# keymap.net
KiCad netlist of a schematic drawn in Altium Designer
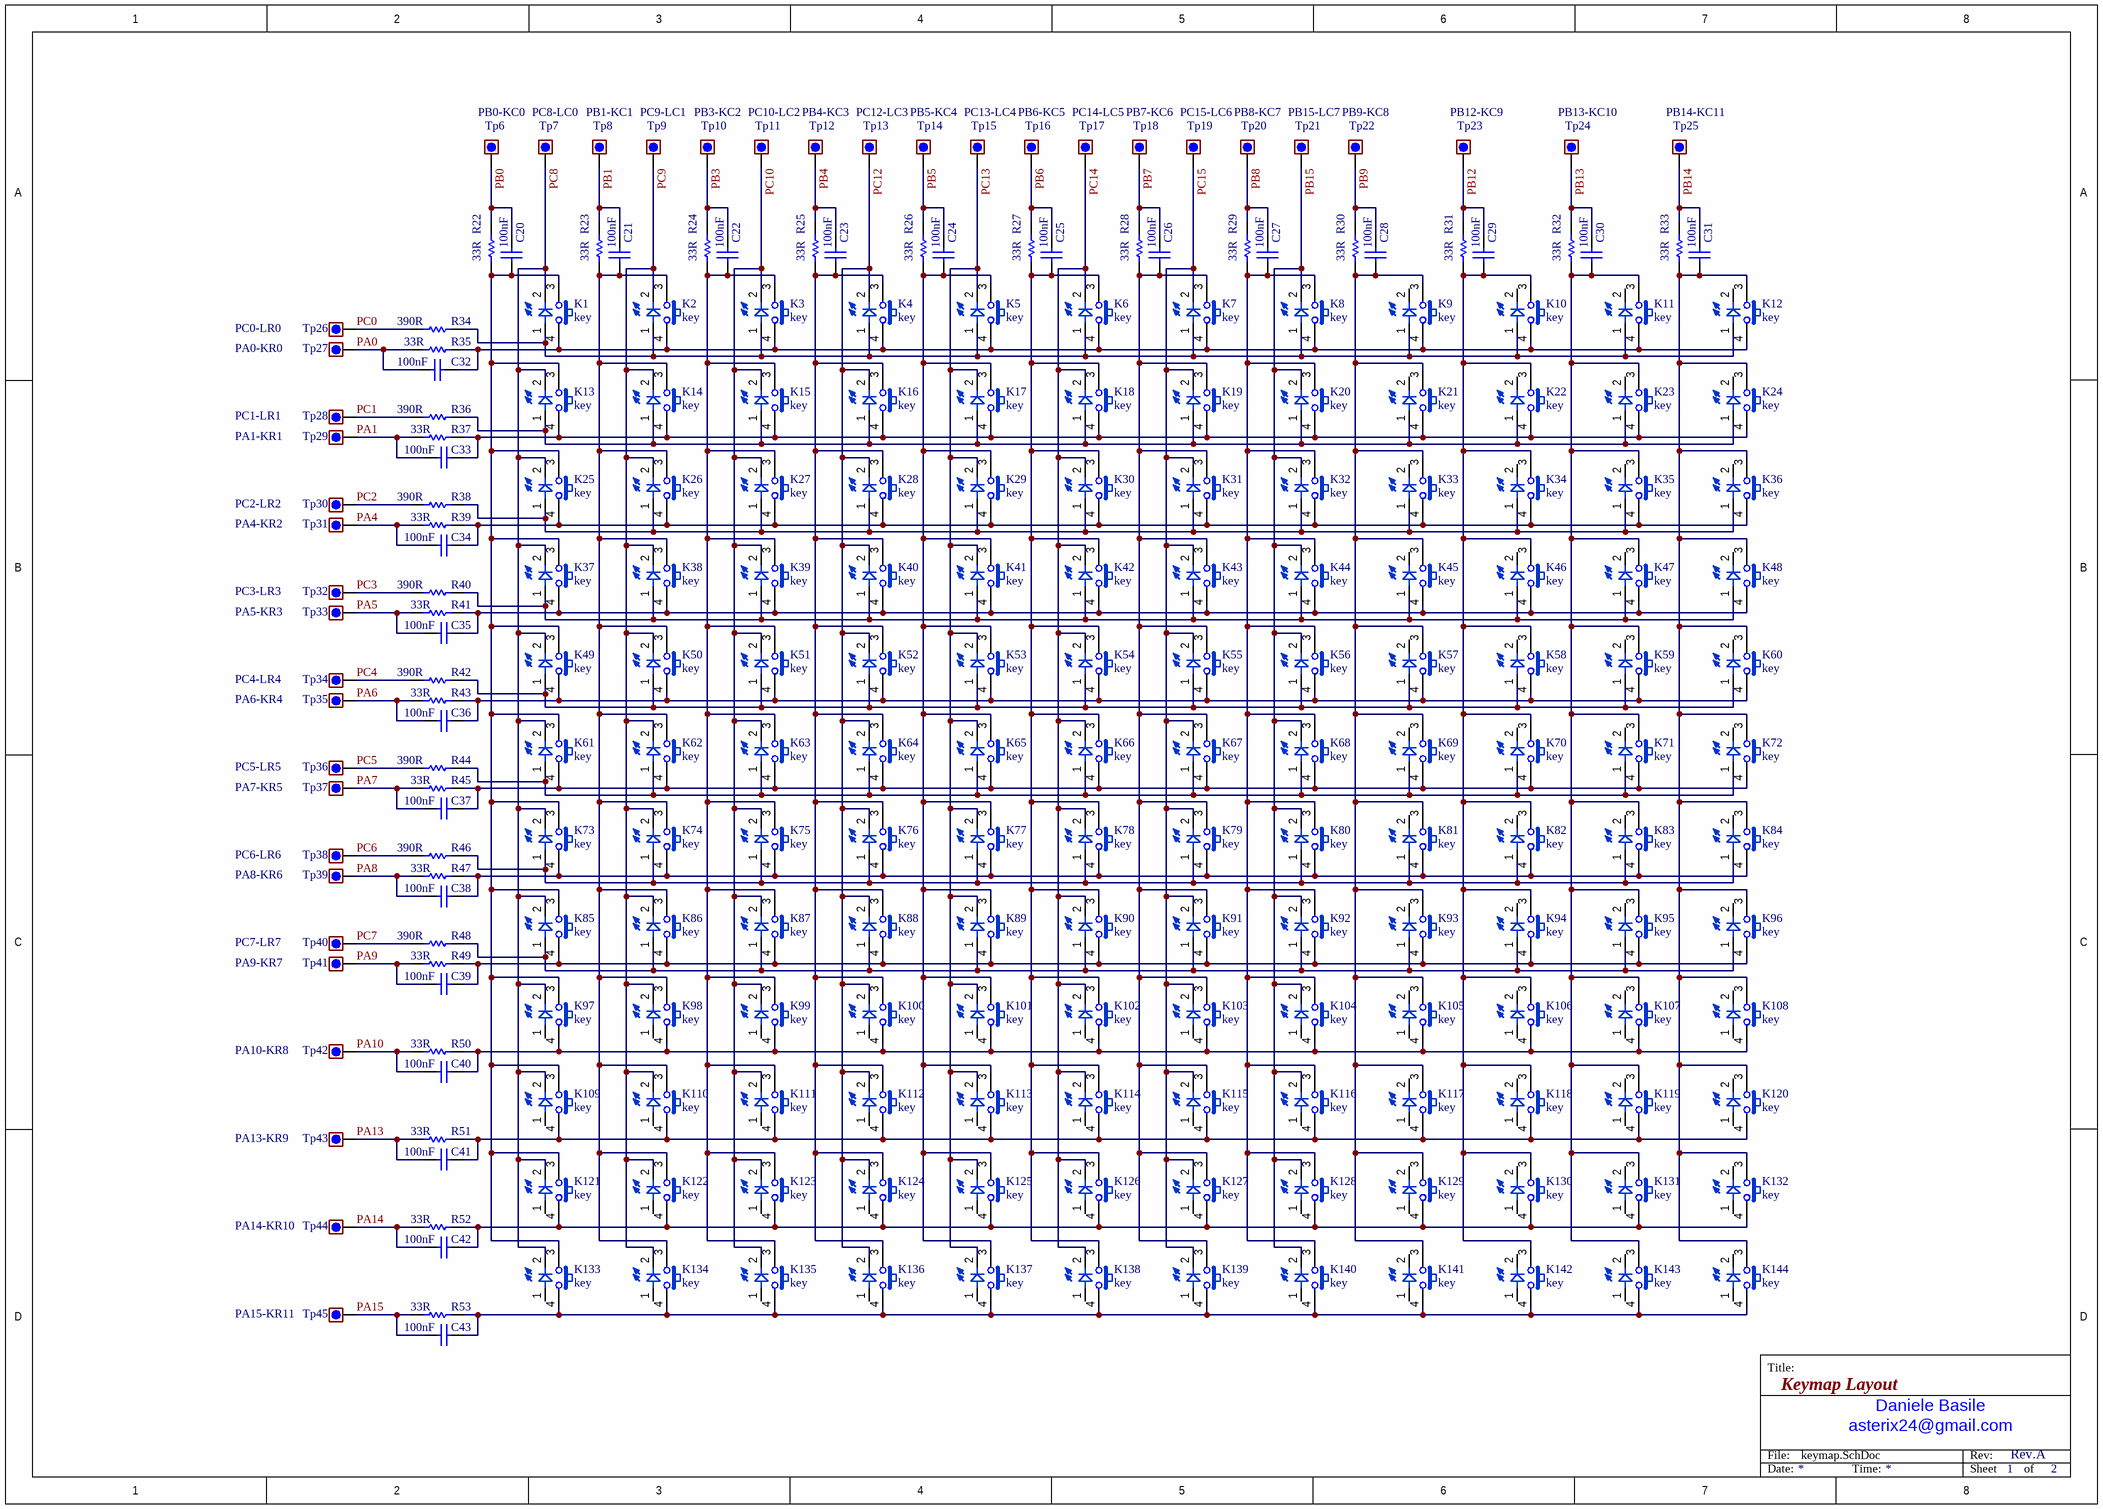
[diagram p0: keymap.SchDoc]

(export (version "E")
  (design (tool "Eeschema 10.0.6"))
  (components
    (comp (ref "C20")
      (value "100nF")
      (footprint "0603_[1608]")
      (description "Ceramic X7R 50V")
      (fields (field (name "PUBLISHER") "Altium Limited"))
      (libsource (lib "DEVELER_Library") (part "Cap"))
    )
    (comp (ref "C21")
      (value "100nF")
      (footprint "0603_[1608]")
      (description "Ceramic X7R 50V")
      (fields (field (name "PUBLISHER") "Altium Limited"))
      (libsource (lib "DEVELER_Library") (part "Cap"))
    )
    (comp (ref "C22")
      (value "100nF")
      (footprint "0603_[1608]")
      (description "Ceramic X7R 50V")
      (fields (field (name "PUBLISHER") "Altium Limited"))
      (libsource (lib "DEVELER_Library") (part "Cap"))
    )
    (comp (ref "C23")
      (value "100nF")
      (footprint "0603_[1608]")
      (description "Ceramic X7R 50V")
      (fields (field (name "PUBLISHER") "Altium Limited"))
      (libsource (lib "DEVELER_Library") (part "Cap"))
    )
    (comp (ref "C24")
      (value "100nF")
      (footprint "0603_[1608]")
      (description "Ceramic X7R 50V")
      (fields (field (name "PUBLISHER") "Altium Limited"))
      (libsource (lib "DEVELER_Library") (part "Cap"))
    )
    (comp (ref "C25")
      (value "100nF")
      (footprint "0603_[1608]")
      (description "Ceramic X7R 50V")
      (fields (field (name "PUBLISHER") "Altium Limited"))
      (libsource (lib "DEVELER_Library") (part "Cap"))
    )
    (comp (ref "C26")
      (value "100nF")
      (footprint "0603_[1608]")
      (description "Ceramic X7R 50V")
      (fields (field (name "PUBLISHER") "Altium Limited"))
      (libsource (lib "DEVELER_Library") (part "Cap"))
    )
    (comp (ref "C27")
      (value "100nF")
      (footprint "0603_[1608]")
      (description "Ceramic X7R 50V")
      (fields (field (name "PUBLISHER") "Altium Limited"))
      (libsource (lib "DEVELER_Library") (part "Cap"))
    )
    (comp (ref "C28")
      (value "100nF")
      (footprint "0603_[1608]")
      (description "Ceramic X7R 50V")
      (fields (field (name "PUBLISHER") "Altium Limited"))
      (libsource (lib "DEVELER_Library") (part "Cap"))
    )
    (comp (ref "C29")
      (value "100nF")
      (footprint "0603_[1608]")
      (description "Ceramic X7R 50V")
      (fields (field (name "PUBLISHER") "Altium Limited"))
      (libsource (lib "DEVELER_Library") (part "Cap"))
    )
    (comp (ref "C30")
      (value "100nF")
      (footprint "0603_[1608]")
      (description "Ceramic X7R 50V")
      (fields (field (name "PUBLISHER") "Altium Limited"))
      (libsource (lib "DEVELER_Library") (part "Cap"))
    )
    (comp (ref "C31")
      (value "100nF")
      (footprint "0603_[1608]")
      (description "Ceramic X7R 50V")
      (fields (field (name "PUBLISHER") "Altium Limited"))
      (libsource (lib "DEVELER_Library") (part "Cap"))
    )
    (comp (ref "C32")
      (value "100nF")
      (footprint "0603_[1608]")
      (description "Ceramic X7R 50V")
      (fields (field (name "PUBLISHER") "Altium Limited"))
      (libsource (lib "DEVELER_Library") (part "Cap"))
    )
    (comp (ref "C33")
      (value "100nF")
      (footprint "0603_[1608]")
      (description "Ceramic X7R 50V")
      (fields (field (name "PUBLISHER") "Altium Limited"))
      (libsource (lib "DEVELER_Library") (part "Cap"))
    )
    (comp (ref "C34")
      (value "100nF")
      (footprint "0603_[1608]")
      (description "Ceramic X7R 50V")
      (fields (field (name "PUBLISHER") "Altium Limited"))
      (libsource (lib "DEVELER_Library") (part "Cap"))
    )
    (comp (ref "C35")
      (value "100nF")
      (footprint "0603_[1608]")
      (description "Ceramic X7R 50V")
      (fields (field (name "PUBLISHER") "Altium Limited"))
      (libsource (lib "DEVELER_Library") (part "Cap"))
    )
    (comp (ref "C36")
      (value "100nF")
      (footprint "0603_[1608]")
      (description "Ceramic X7R 50V")
      (fields (field (name "PUBLISHER") "Altium Limited"))
      (libsource (lib "DEVELER_Library") (part "Cap"))
    )
    (comp (ref "C37")
      (value "100nF")
      (footprint "0603_[1608]")
      (description "Ceramic X7R 50V")
      (fields (field (name "PUBLISHER") "Altium Limited"))
      (libsource (lib "DEVELER_Library") (part "Cap"))
    )
    (comp (ref "C38")
      (value "100nF")
      (footprint "0603_[1608]")
      (description "Ceramic X7R 50V")
      (fields (field (name "PUBLISHER") "Altium Limited"))
      (libsource (lib "DEVELER_Library") (part "Cap"))
    )
    (comp (ref "C39")
      (value "100nF")
      (footprint "0603_[1608]")
      (description "Ceramic X7R 50V")
      (fields (field (name "PUBLISHER") "Altium Limited"))
      (libsource (lib "DEVELER_Library") (part "Cap"))
    )
    (comp (ref "C40")
      (value "100nF")
      (footprint "0603_[1608]")
      (description "Ceramic X7R 50V")
      (fields (field (name "PUBLISHER") "Altium Limited"))
      (libsource (lib "DEVELER_Library") (part "Cap"))
    )
    (comp (ref "C41")
      (value "100nF")
      (footprint "0603_[1608]")
      (description "Ceramic X7R 50V")
      (fields (field (name "PUBLISHER") "Altium Limited"))
      (libsource (lib "DEVELER_Library") (part "Cap"))
    )
    (comp (ref "C42")
      (value "100nF")
      (footprint "0603_[1608]")
      (description "Ceramic X7R 50V")
      (fields (field (name "PUBLISHER") "Altium Limited"))
      (libsource (lib "DEVELER_Library") (part "Cap"))
    )
    (comp (ref "C43")
      (value "100nF")
      (footprint "0603_[1608]")
      (description "Ceramic X7R 50V")
      (fields (field (name "PUBLISHER") "Altium Limited"))
      (libsource (lib "DEVELER_Library") (part "Cap"))
    )
    (comp (ref "K1")
      (value "key")
      (description "CherryMx key button.")
      (libsource (lib "develer_library") (part "keybutton_cherryMX"))
    )
    (comp (ref "K2")
      (value "key")
      (description "CherryMx key button.")
      (libsource (lib "develer_library") (part "keybutton_cherryMX"))
    )
    (comp (ref "K3")
      (value "key")
      (description "CherryMx key button.")
      (libsource (lib "develer_library") (part "keybutton_cherryMX"))
    )
    (comp (ref "K4")
      (value "key")
      (description "CherryMx key button.")
      (libsource (lib "develer_library") (part "keybutton_cherryMX"))
    )
    (comp (ref "K5")
      (value "key")
      (description "CherryMx key button.")
      (libsource (lib "develer_library") (part "keybutton_cherryMX"))
    )
    (comp (ref "K6")
      (value "key")
      (description "CherryMx key button.")
      (libsource (lib "develer_library") (part "keybutton_cherryMX"))
    )
    (comp (ref "K7")
      (value "key")
      (description "CherryMx key button.")
      (libsource (lib "develer_library") (part "keybutton_cherryMX"))
    )
    (comp (ref "K8")
      (value "key")
      (description "CherryMx key button.")
      (libsource (lib "develer_library") (part "keybutton_cherryMX"))
    )
    (comp (ref "K9")
      (value "key")
      (description "CherryMx key button.")
      (libsource (lib "develer_library") (part "keybutton_cherryMX"))
    )
    (comp (ref "K10")
      (value "key")
      (description "CherryMx key button.")
      (libsource (lib "develer_library") (part "keybutton_cherryMX"))
    )
    (comp (ref "K11")
      (value "key")
      (description "CherryMx key button.")
      (libsource (lib "develer_library") (part "keybutton_cherryMX"))
    )
    (comp (ref "K12")
      (value "key")
      (description "CherryMx key button.")
      (libsource (lib "develer_library") (part "keybutton_cherryMX"))
    )
    (comp (ref "K13")
      (value "key")
      (description "CherryMx key button.")
      (libsource (lib "develer_library") (part "keybutton_cherryMX"))
    )
    (comp (ref "K14")
      (value "key")
      (description "CherryMx key button.")
      (libsource (lib "develer_library") (part "keybutton_cherryMX"))
    )
    (comp (ref "K15")
      (value "key")
      (description "CherryMx key button.")
      (libsource (lib "develer_library") (part "keybutton_cherryMX"))
    )
    (comp (ref "K16")
      (value "key")
      (description "CherryMx key button.")
      (libsource (lib "develer_library") (part "keybutton_cherryMX"))
    )
    (comp (ref "K17")
      (value "key")
      (description "CherryMx key button.")
      (libsource (lib "develer_library") (part "keybutton_cherryMX"))
    )
    (comp (ref "K18")
      (value "key")
      (description "CherryMx key button.")
      (libsource (lib "develer_library") (part "keybutton_cherryMX"))
    )
    (comp (ref "K19")
      (value "key")
      (description "CherryMx key button.")
      (libsource (lib "develer_library") (part "keybutton_cherryMX"))
    )
    (comp (ref "K20")
      (value "key")
      (description "CherryMx key button.")
      (libsource (lib "develer_library") (part "keybutton_cherryMX"))
    )
    (comp (ref "K21")
      (value "key")
      (description "CherryMx key button.")
      (libsource (lib "develer_library") (part "keybutton_cherryMX"))
    )
    (comp (ref "K22")
      (value "key")
      (description "CherryMx key button.")
      (libsource (lib "develer_library") (part "keybutton_cherryMX"))
    )
    (comp (ref "K23")
      (value "key")
      (description "CherryMx key button.")
      (libsource (lib "develer_library") (part "keybutton_cherryMX"))
    )
    (comp (ref "K24")
      (value "key")
      (description "CherryMx key button.")
      (libsource (lib "develer_library") (part "keybutton_cherryMX"))
    )
    (comp (ref "K25")
      (value "key")
      (description "CherryMx key button.")
      (libsource (lib "develer_library") (part "keybutton_cherryMX"))
    )
    (comp (ref "K26")
      (value "key")
      (description "CherryMx key button.")
      (libsource (lib "develer_library") (part "keybutton_cherryMX"))
    )
    (comp (ref "K27")
      (value "key")
      (description "CherryMx key button.")
      (libsource (lib "develer_library") (part "keybutton_cherryMX"))
    )
    (comp (ref "K28")
      (value "key")
      (description "CherryMx key button.")
      (libsource (lib "develer_library") (part "keybutton_cherryMX"))
    )
    (comp (ref "K29")
      (value "key")
      (description "CherryMx key button.")
      (libsource (lib "develer_library") (part "keybutton_cherryMX"))
    )
    (comp (ref "K30")
      (value "key")
      (description "CherryMx key button.")
      (libsource (lib "develer_library") (part "keybutton_cherryMX"))
    )
    (comp (ref "K31")
      (value "key")
      (description "CherryMx key button.")
      (libsource (lib "develer_library") (part "keybutton_cherryMX"))
    )
    (comp (ref "K32")
      (value "key")
      (description "CherryMx key button.")
      (libsource (lib "develer_library") (part "keybutton_cherryMX"))
    )
    (comp (ref "K33")
      (value "key")
      (description "CherryMx key button.")
      (libsource (lib "develer_library") (part "keybutton_cherryMX"))
    )
    (comp (ref "K34")
      (value "key")
      (description "CherryMx key button.")
      (libsource (lib "develer_library") (part "keybutton_cherryMX"))
    )
    (comp (ref "K35")
      (value "key")
      (description "CherryMx key button.")
      (libsource (lib "develer_library") (part "keybutton_cherryMX"))
    )
    (comp (ref "K36")
      (value "key")
      (description "CherryMx key button.")
      (libsource (lib "develer_library") (part "keybutton_cherryMX"))
    )
    (comp (ref "K37")
      (value "key")
      (description "CherryMx key button.")
      (libsource (lib "develer_library") (part "keybutton_cherryMX"))
    )
    (comp (ref "K38")
      (value "key")
      (description "CherryMx key button.")
      (libsource (lib "develer_library") (part "keybutton_cherryMX"))
    )
    (comp (ref "K39")
      (value "key")
      (description "CherryMx key button.")
      (libsource (lib "develer_library") (part "keybutton_cherryMX"))
    )
    (comp (ref "K40")
      (value "key")
      (description "CherryMx key button.")
      (libsource (lib "develer_library") (part "keybutton_cherryMX"))
    )
    (comp (ref "K41")
      (value "key")
      (description "CherryMx key button.")
      (libsource (lib "develer_library") (part "keybutton_cherryMX"))
    )
    (comp (ref "K42")
      (value "key")
      (description "CherryMx key button.")
      (libsource (lib "develer_library") (part "keybutton_cherryMX"))
    )
    (comp (ref "K43")
      (value "key")
      (description "CherryMx key button.")
      (libsource (lib "develer_library") (part "keybutton_cherryMX"))
    )
    (comp (ref "K44")
      (value "key")
      (description "CherryMx key button.")
      (libsource (lib "develer_library") (part "keybutton_cherryMX"))
    )
    (comp (ref "K45")
      (value "key")
      (description "CherryMx key button.")
      (libsource (lib "develer_library") (part "keybutton_cherryMX"))
    )
    (comp (ref "K46")
      (value "key")
      (description "CherryMx key button.")
      (libsource (lib "develer_library") (part "keybutton_cherryMX"))
    )
    (comp (ref "K47")
      (value "key")
      (description "CherryMx key button.")
      (libsource (lib "develer_library") (part "keybutton_cherryMX"))
    )
    (comp (ref "K48")
      (value "key")
      (description "CherryMx key button.")
      (libsource (lib "develer_library") (part "keybutton_cherryMX"))
    )
    (comp (ref "K49")
      (value "key")
      (description "CherryMx key button.")
      (libsource (lib "develer_library") (part "keybutton_cherryMX"))
    )
    (comp (ref "K50")
      (value "key")
      (description "CherryMx key button.")
      (libsource (lib "develer_library") (part "keybutton_cherryMX"))
    )
    (comp (ref "K51")
      (value "key")
      (description "CherryMx key button.")
      (libsource (lib "develer_library") (part "keybutton_cherryMX"))
    )
    (comp (ref "K52")
      (value "key")
      (description "CherryMx key button.")
      (libsource (lib "develer_library") (part "keybutton_cherryMX"))
    )
    (comp (ref "K53")
      (value "key")
      (description "CherryMx key button.")
      (libsource (lib "develer_library") (part "keybutton_cherryMX"))
    )
    (comp (ref "K54")
      (value "key")
      (description "CherryMx key button.")
      (libsource (lib "develer_library") (part "keybutton_cherryMX"))
    )
    (comp (ref "K55")
      (value "key")
      (description "CherryMx key button.")
      (libsource (lib "develer_library") (part "keybutton_cherryMX"))
    )
    (comp (ref "K56")
      (value "key")
      (description "CherryMx key button.")
      (libsource (lib "develer_library") (part "keybutton_cherryMX"))
    )
    (comp (ref "K57")
      (value "key")
      (description "CherryMx key button.")
      (libsource (lib "develer_library") (part "keybutton_cherryMX"))
    )
    (comp (ref "K58")
      (value "key")
      (description "CherryMx key button.")
      (libsource (lib "develer_library") (part "keybutton_cherryMX"))
    )
    (comp (ref "K59")
      (value "key")
      (description "CherryMx key button.")
      (libsource (lib "develer_library") (part "keybutton_cherryMX"))
    )
    (comp (ref "K60")
      (value "key")
      (description "CherryMx key button.")
      (libsource (lib "develer_library") (part "keybutton_cherryMX"))
    )
    (comp (ref "K61")
      (value "key")
      (description "CherryMx key button.")
      (libsource (lib "develer_library") (part "keybutton_cherryMX"))
    )
    (comp (ref "K62")
      (value "key")
      (description "CherryMx key button.")
      (libsource (lib "develer_library") (part "keybutton_cherryMX"))
    )
    (comp (ref "K63")
      (value "key")
      (description "CherryMx key button.")
      (libsource (lib "develer_library") (part "keybutton_cherryMX"))
    )
    (comp (ref "K64")
      (value "key")
      (description "CherryMx key button.")
      (libsource (lib "develer_library") (part "keybutton_cherryMX"))
    )
    (comp (ref "K65")
      (value "key")
      (description "CherryMx key button.")
      (libsource (lib "develer_library") (part "keybutton_cherryMX"))
    )
    (comp (ref "K66")
      (value "key")
      (description "CherryMx key button.")
      (libsource (lib "develer_library") (part "keybutton_cherryMX"))
    )
    (comp (ref "K67")
      (value "key")
      (description "CherryMx key button.")
      (libsource (lib "develer_library") (part "keybutton_cherryMX"))
    )
    (comp (ref "K68")
      (value "key")
      (description "CherryMx key button.")
      (libsource (lib "develer_library") (part "keybutton_cherryMX"))
    )
    (comp (ref "K69")
      (value "key")
      (description "CherryMx key button.")
      (libsource (lib "develer_library") (part "keybutton_cherryMX"))
    )
    (comp (ref "K70")
      (value "key")
      (description "CherryMx key button.")
      (libsource (lib "develer_library") (part "keybutton_cherryMX"))
    )
    (comp (ref "K71")
      (value "key")
      (description "CherryMx key button.")
      (libsource (lib "develer_library") (part "keybutton_cherryMX"))
    )
    (comp (ref "K72")
      (value "key")
      (description "CherryMx key button.")
      (libsource (lib "develer_library") (part "keybutton_cherryMX"))
    )
    (comp (ref "K73")
      (value "key")
      (description "CherryMx key button.")
      (libsource (lib "develer_library") (part "keybutton_cherryMX"))
    )
    (comp (ref "K74")
      (value "key")
      (description "CherryMx key button.")
      (libsource (lib "develer_library") (part "keybutton_cherryMX"))
    )
    (comp (ref "K75")
      (value "key")
      (description "CherryMx key button.")
      (libsource (lib "develer_library") (part "keybutton_cherryMX"))
    )
    (comp (ref "K76")
      (value "key")
      (description "CherryMx key button.")
      (libsource (lib "develer_library") (part "keybutton_cherryMX"))
    )
    (comp (ref "K77")
      (value "key")
      (description "CherryMx key button.")
      (libsource (lib "develer_library") (part "keybutton_cherryMX"))
    )
    (comp (ref "K78")
      (value "key")
      (description "CherryMx key button.")
      (libsource (lib "develer_library") (part "keybutton_cherryMX"))
    )
    (comp (ref "K79")
      (value "key")
      (description "CherryMx key button.")
      (libsource (lib "develer_library") (part "keybutton_cherryMX"))
    )
    (comp (ref "K80")
      (value "key")
      (description "CherryMx key button.")
      (libsource (lib "develer_library") (part "keybutton_cherryMX"))
    )
    (comp (ref "K81")
      (value "key")
      (description "CherryMx key button.")
      (libsource (lib "develer_library") (part "keybutton_cherryMX"))
    )
    (comp (ref "K82")
      (value "key")
      (description "CherryMx key button.")
      (libsource (lib "develer_library") (part "keybutton_cherryMX"))
    )
    (comp (ref "K83")
      (value "key")
      (description "CherryMx key button.")
      (libsource (lib "develer_library") (part "keybutton_cherryMX"))
    )
    (comp (ref "K84")
      (value "key")
      (description "CherryMx key button.")
      (libsource (lib "develer_library") (part "keybutton_cherryMX"))
    )
    (comp (ref "K85")
      (value "key")
      (description "CherryMx key button.")
      (libsource (lib "develer_library") (part "keybutton_cherryMX"))
    )
    (comp (ref "K86")
      (value "key")
      (description "CherryMx key button.")
      (libsource (lib "develer_library") (part "keybutton_cherryMX"))
    )
    (comp (ref "K87")
      (value "key")
      (description "CherryMx key button.")
      (libsource (lib "develer_library") (part "keybutton_cherryMX"))
    )
    (comp (ref "K88")
      (value "key")
      (description "CherryMx key button.")
      (libsource (lib "develer_library") (part "keybutton_cherryMX"))
    )
    (comp (ref "K89")
      (value "key")
      (description "CherryMx key button.")
      (libsource (lib "develer_library") (part "keybutton_cherryMX"))
    )
    (comp (ref "K90")
      (value "key")
      (description "CherryMx key button.")
      (libsource (lib "develer_library") (part "keybutton_cherryMX"))
    )
    (comp (ref "K91")
      (value "key")
      (description "CherryMx key button.")
      (libsource (lib "develer_library") (part "keybutton_cherryMX"))
    )
    (comp (ref "K92")
      (value "key")
      (description "CherryMx key button.")
      (libsource (lib "develer_library") (part "keybutton_cherryMX"))
    )
    (comp (ref "K93")
      (value "key")
      (description "CherryMx key button.")
      (libsource (lib "develer_library") (part "keybutton_cherryMX"))
    )
    (comp (ref "K94")
      (value "key")
      (description "CherryMx key button.")
      (libsource (lib "develer_library") (part "keybutton_cherryMX"))
    )
    (comp (ref "K95")
      (value "key")
      (description "CherryMx key button.")
      (libsource (lib "develer_library") (part "keybutton_cherryMX"))
    )
    (comp (ref "K96")
      (value "key")
      (description "CherryMx key button.")
      (libsource (lib "develer_library") (part "keybutton_cherryMX"))
    )
    (comp (ref "K97")
      (value "key")
      (description "CherryMx key button.")
      (libsource (lib "develer_library") (part "keybutton_cherryMX"))
    )
    (comp (ref "K98")
      (value "key")
      (description "CherryMx key button.")
      (libsource (lib "develer_library") (part "keybutton_cherryMX"))
    )
    (comp (ref "K99")
      (value "key")
      (description "CherryMx key button.")
      (libsource (lib "develer_library") (part "keybutton_cherryMX"))
    )
    (comp (ref "K100")
      (value "key")
      (description "CherryMx key button.")
      (libsource (lib "develer_library") (part "keybutton_cherryMX"))
    )
    (comp (ref "K101")
      (value "key")
      (description "CherryMx key button.")
      (libsource (lib "develer_library") (part "keybutton_cherryMX"))
    )
    (comp (ref "K102")
      (value "key")
      (description "CherryMx key button.")
      (libsource (lib "develer_library") (part "keybutton_cherryMX"))
    )
    (comp (ref "K103")
      (value "key")
      (description "CherryMx key button.")
      (libsource (lib "develer_library") (part "keybutton_cherryMX"))
    )
    (comp (ref "K104")
      (value "key")
      (description "CherryMx key button.")
      (libsource (lib "develer_library") (part "keybutton_cherryMX"))
    )
    (comp (ref "K105")
      (value "key")
      (description "CherryMx key button.")
      (libsource (lib "develer_library") (part "keybutton_cherryMX"))
    )
    (comp (ref "K106")
      (value "key")
      (description "CherryMx key button.")
      (libsource (lib "develer_library") (part "keybutton_cherryMX"))
    )
    (comp (ref "K107")
      (value "key")
      (description "CherryMx key button.")
      (libsource (lib "develer_library") (part "keybutton_cherryMX"))
    )
    (comp (ref "K108")
      (value "key")
      (description "CherryMx key button.")
      (libsource (lib "develer_library") (part "keybutton_cherryMX"))
    )
    (comp (ref "K109")
      (value "key")
      (description "CherryMx key button.")
      (libsource (lib "develer_library") (part "keybutton_cherryMX"))
    )
    (comp (ref "K110")
      (value "key")
      (description "CherryMx key button.")
      (libsource (lib "develer_library") (part "keybutton_cherryMX"))
    )
    (comp (ref "K111")
      (value "key")
      (description "CherryMx key button.")
      (libsource (lib "develer_library") (part "keybutton_cherryMX"))
    )
    (comp (ref "K112")
      (value "key")
      (description "CherryMx key button.")
      (libsource (lib "develer_library") (part "keybutton_cherryMX"))
    )
    (comp (ref "K113")
      (value "key")
      (description "CherryMx key button.")
      (libsource (lib "develer_library") (part "keybutton_cherryMX"))
    )
    (comp (ref "K114")
      (value "key")
      (description "CherryMx key button.")
      (libsource (lib "develer_library") (part "keybutton_cherryMX"))
    )
    (comp (ref "K115")
      (value "key")
      (description "CherryMx key button.")
      (libsource (lib "develer_library") (part "keybutton_cherryMX"))
    )
    (comp (ref "K116")
      (value "key")
      (description "CherryMx key button.")
      (libsource (lib "develer_library") (part "keybutton_cherryMX"))
    )
    (comp (ref "K117")
      (value "key")
      (description "CherryMx key button.")
      (libsource (lib "develer_library") (part "keybutton_cherryMX"))
    )
    (comp (ref "K118")
      (value "key")
      (description "CherryMx key button.")
      (libsource (lib "develer_library") (part "keybutton_cherryMX"))
    )
    (comp (ref "K119")
      (value "key")
      (description "CherryMx key button.")
      (libsource (lib "develer_library") (part "keybutton_cherryMX"))
    )
    (comp (ref "K120")
      (value "key")
      (description "CherryMx key button.")
      (libsource (lib "develer_library") (part "keybutton_cherryMX"))
    )
    (comp (ref "K121")
      (value "key")
      (description "CherryMx key button.")
      (libsource (lib "develer_library") (part "keybutton_cherryMX"))
    )
    (comp (ref "K122")
      (value "key")
      (description "CherryMx key button.")
      (libsource (lib "develer_library") (part "keybutton_cherryMX"))
    )
    (comp (ref "K123")
      (value "key")
      (description "CherryMx key button.")
      (libsource (lib "develer_library") (part "keybutton_cherryMX"))
    )
    (comp (ref "K124")
      (value "key")
      (description "CherryMx key button.")
      (libsource (lib "develer_library") (part "keybutton_cherryMX"))
    )
    (comp (ref "K125")
      (value "key")
      (description "CherryMx key button.")
      (libsource (lib "develer_library") (part "keybutton_cherryMX"))
    )
    (comp (ref "K126")
      (value "key")
      (description "CherryMx key button.")
      (libsource (lib "develer_library") (part "keybutton_cherryMX"))
    )
    (comp (ref "K127")
      (value "key")
      (description "CherryMx key button.")
      (libsource (lib "develer_library") (part "keybutton_cherryMX"))
    )
    (comp (ref "K128")
      (value "key")
      (description "CherryMx key button.")
      (libsource (lib "develer_library") (part "keybutton_cherryMX"))
    )
    (comp (ref "K129")
      (value "key")
      (description "CherryMx key button.")
      (libsource (lib "develer_library") (part "keybutton_cherryMX"))
    )
    (comp (ref "K130")
      (value "key")
      (description "CherryMx key button.")
      (libsource (lib "develer_library") (part "keybutton_cherryMX"))
    )
    (comp (ref "K131")
      (value "key")
      (description "CherryMx key button.")
      (libsource (lib "develer_library") (part "keybutton_cherryMX"))
    )
    (comp (ref "K132")
      (value "key")
      (description "CherryMx key button.")
      (libsource (lib "develer_library") (part "keybutton_cherryMX"))
    )
    (comp (ref "K133")
      (value "key")
      (description "CherryMx key button.")
      (libsource (lib "develer_library") (part "keybutton_cherryMX"))
    )
    (comp (ref "K134")
      (value "key")
      (description "CherryMx key button.")
      (libsource (lib "develer_library") (part "keybutton_cherryMX"))
    )
    (comp (ref "K135")
      (value "key")
      (description "CherryMx key button.")
      (libsource (lib "develer_library") (part "keybutton_cherryMX"))
    )
    (comp (ref "K136")
      (value "key")
      (description "CherryMx key button.")
      (libsource (lib "develer_library") (part "keybutton_cherryMX"))
    )
    (comp (ref "K137")
      (value "key")
      (description "CherryMx key button.")
      (libsource (lib "develer_library") (part "keybutton_cherryMX"))
    )
    (comp (ref "K138")
      (value "key")
      (description "CherryMx key button.")
      (libsource (lib "develer_library") (part "keybutton_cherryMX"))
    )
    (comp (ref "K139")
      (value "key")
      (description "CherryMx key button.")
      (libsource (lib "develer_library") (part "keybutton_cherryMX"))
    )
    (comp (ref "K140")
      (value "key")
      (description "CherryMx key button.")
      (libsource (lib "develer_library") (part "keybutton_cherryMX"))
    )
    (comp (ref "K141")
      (value "key")
      (description "CherryMx key button.")
      (libsource (lib "develer_library") (part "keybutton_cherryMX"))
    )
    (comp (ref "K142")
      (value "key")
      (description "CherryMx key button.")
      (libsource (lib "develer_library") (part "keybutton_cherryMX"))
    )
    (comp (ref "K143")
      (value "key")
      (description "CherryMx key button.")
      (libsource (lib "develer_library") (part "keybutton_cherryMX"))
    )
    (comp (ref "K144")
      (value "key")
      (description "CherryMx key button.")
      (libsource (lib "develer_library") (part "keybutton_cherryMX"))
    )
    (comp (ref "R22")
      (value "33R")
      (footprint "0402_[1005]")
      (description "Resistor")
      (fields (field (name "PUBLISHER") "Altium Limited"))
      (libsource (lib "simboli") (part "Res1"))
    )
    (comp (ref "R23")
      (value "33R")
      (footprint "0402_[1005]")
      (description "Resistor")
      (fields (field (name "PUBLISHER") "Altium Limited"))
      (libsource (lib "simboli") (part "Res1"))
    )
    (comp (ref "R24")
      (value "33R")
      (footprint "0402_[1005]")
      (description "Resistor")
      (fields (field (name "PUBLISHER") "Altium Limited"))
      (libsource (lib "simboli") (part "Res1"))
    )
    (comp (ref "R25")
      (value "33R")
      (footprint "0402_[1005]")
      (description "Resistor")
      (fields (field (name "PUBLISHER") "Altium Limited"))
      (libsource (lib "simboli") (part "Res1"))
    )
    (comp (ref "R26")
      (value "33R")
      (footprint "0402_[1005]")
      (description "Resistor")
      (fields (field (name "PUBLISHER") "Altium Limited"))
      (libsource (lib "simboli") (part "Res1"))
    )
    (comp (ref "R27")
      (value "33R")
      (footprint "0402_[1005]")
      (description "Resistor")
      (fields (field (name "PUBLISHER") "Altium Limited"))
      (libsource (lib "simboli") (part "Res1"))
    )
    (comp (ref "R28")
      (value "33R")
      (footprint "0402_[1005]")
      (description "Resistor")
      (fields (field (name "PUBLISHER") "Altium Limited"))
      (libsource (lib "simboli") (part "Res1"))
    )
    (comp (ref "R29")
      (value "33R")
      (footprint "0402_[1005]")
      (description "Resistor")
      (fields (field (name "PUBLISHER") "Altium Limited"))
      (libsource (lib "simboli") (part "Res1"))
    )
    (comp (ref "R30")
      (value "33R")
      (footprint "0402_[1005]")
      (description "Resistor")
      (fields (field (name "PUBLISHER") "Altium Limited"))
      (libsource (lib "simboli") (part "Res1"))
    )
    (comp (ref "R31")
      (value "33R")
      (footprint "0402_[1005]")
      (description "Resistor")
      (fields (field (name "PUBLISHER") "Altium Limited"))
      (libsource (lib "simboli") (part "Res1"))
    )
    (comp (ref "R32")
      (value "33R")
      (footprint "0402_[1005]")
      (description "Resistor")
      (fields (field (name "PUBLISHER") "Altium Limited"))
      (libsource (lib "simboli") (part "Res1"))
    )
    (comp (ref "R33")
      (value "33R")
      (footprint "0402_[1005]")
      (description "Resistor")
      (fields (field (name "PUBLISHER") "Altium Limited"))
      (libsource (lib "simboli") (part "Res1"))
    )
    (comp (ref "R34")
      (value "390R")
      (footprint "0402_[1005]")
      (description "Resistor")
      (fields (field (name "PUBLISHER") "Altium Limited"))
      (libsource (lib "simboli") (part "Res1"))
    )
    (comp (ref "R35")
      (value "33R")
      (footprint "0402_[1005]")
      (description "Resistor")
      (fields (field (name "PUBLISHER") "Altium Limited"))
      (libsource (lib "simboli") (part "Res1"))
    )
    (comp (ref "R36")
      (value "390R")
      (footprint "0402_[1005]")
      (description "Resistor")
      (fields (field (name "PUBLISHER") "Altium Limited"))
      (libsource (lib "simboli") (part "Res1"))
    )
    (comp (ref "R37")
      (value "33R")
      (footprint "0402_[1005]")
      (description "Resistor")
      (fields (field (name "PUBLISHER") "Altium Limited"))
      (libsource (lib "simboli") (part "Res1"))
    )
    (comp (ref "R38")
      (value "390R")
      (footprint "0402_[1005]")
      (description "Resistor")
      (fields (field (name "PUBLISHER") "Altium Limited"))
      (libsource (lib "simboli") (part "Res1"))
    )
    (comp (ref "R39")
      (value "33R")
      (footprint "0402_[1005]")
      (description "Resistor")
      (fields (field (name "PUBLISHER") "Altium Limited"))
      (libsource (lib "simboli") (part "Res1"))
    )
    (comp (ref "R40")
      (value "390R")
      (footprint "0402_[1005]")
      (description "Resistor")
      (fields (field (name "PUBLISHER") "Altium Limited"))
      (libsource (lib "simboli") (part "Res1"))
    )
    (comp (ref "R41")
      (value "33R")
      (footprint "0402_[1005]")
      (description "Resistor")
      (fields (field (name "PUBLISHER") "Altium Limited"))
      (libsource (lib "simboli") (part "Res1"))
    )
    (comp (ref "R42")
      (value "390R")
      (footprint "0402_[1005]")
      (description "Resistor")
      (fields (field (name "PUBLISHER") "Altium Limited"))
      (libsource (lib "simboli") (part "Res1"))
    )
    (comp (ref "R43")
      (value "33R")
      (footprint "0402_[1005]")
      (description "Resistor")
      (fields (field (name "PUBLISHER") "Altium Limited"))
      (libsource (lib "simboli") (part "Res1"))
    )
    (comp (ref "R44")
      (value "390R")
      (footprint "0402_[1005]")
      (description "Resistor")
      (fields (field (name "PUBLISHER") "Altium Limited"))
      (libsource (lib "simboli") (part "Res1"))
    )
    (comp (ref "R45")
      (value "33R")
      (footprint "0402_[1005]")
      (description "Resistor")
      (fields (field (name "PUBLISHER") "Altium Limited"))
      (libsource (lib "simboli") (part "Res1"))
    )
    (comp (ref "R46")
      (value "390R")
      (footprint "0402_[1005]")
      (description "Resistor")
      (fields (field (name "PUBLISHER") "Altium Limited"))
      (libsource (lib "simboli") (part "Res1"))
    )
    (comp (ref "R47")
      (value "33R")
      (footprint "0402_[1005]")
      (description "Resistor")
      (fields (field (name "PUBLISHER") "Altium Limited"))
      (libsource (lib "simboli") (part "Res1"))
    )
    (comp (ref "R48")
      (value "390R")
      (footprint "0402_[1005]")
      (description "Resistor")
      (fields (field (name "PUBLISHER") "Altium Limited"))
      (libsource (lib "simboli") (part "Res1"))
    )
    (comp (ref "R49")
      (value "33R")
      (footprint "0402_[1005]")
      (description "Resistor")
      (fields (field (name "PUBLISHER") "Altium Limited"))
      (libsource (lib "simboli") (part "Res1"))
    )
    (comp (ref "R50")
      (value "33R")
      (footprint "0402_[1005]")
      (description "Resistor")
      (fields (field (name "PUBLISHER") "Altium Limited"))
      (libsource (lib "simboli") (part "Res1"))
    )
    (comp (ref "R51")
      (value "33R")
      (footprint "0402_[1005]")
      (description "Resistor")
      (fields (field (name "PUBLISHER") "Altium Limited"))
      (libsource (lib "simboli") (part "Res1"))
    )
    (comp (ref "R52")
      (value "33R")
      (footprint "0402_[1005]")
      (description "Resistor")
      (fields (field (name "PUBLISHER") "Altium Limited"))
      (libsource (lib "simboli") (part "Res1"))
    )
    (comp (ref "R53")
      (value "33R")
      (footprint "0402_[1005]")
      (description "Resistor")
      (fields (field (name "PUBLISHER") "Altium Limited"))
      (libsource (lib "simboli") (part "Res1"))
    )
    (comp (ref "Tp6")
      (value "PB0-KC0")
      (footprint "TEST_POINT_THD_D1.8MM")
      (description "Test point")
      (libsource (lib "") (part "Test_point_1"))
    )
    (comp (ref "Tp7")
      (value "PC8-LC0")
      (footprint "TEST_POINT_THD_D1.8MM")
      (description "Test point")
      (libsource (lib "") (part "Test_point_1"))
    )
    (comp (ref "Tp8")
      (value "PB1-KC1")
      (footprint "TEST_POINT_THD_D1.8MM")
      (description "Test point")
      (libsource (lib "") (part "Test_point_1"))
    )
    (comp (ref "Tp9")
      (value "PC9-LC1")
      (footprint "TEST_POINT_THD_D1.8MM")
      (description "Test point")
      (libsource (lib "") (part "Test_point_1"))
    )
    (comp (ref "Tp10")
      (value "PB3-KC2")
      (footprint "TEST_POINT_THD_D1.8MM")
      (description "Test point")
      (libsource (lib "") (part "Test_point_1"))
    )
    (comp (ref "Tp11")
      (value "PC10-LC2")
      (footprint "TEST_POINT_THD_D1.8MM")
      (description "Test point")
      (libsource (lib "") (part "Test_point_1"))
    )
    (comp (ref "Tp12")
      (value "PB4-KC3")
      (footprint "TEST_POINT_THD_D1.8MM")
      (description "Test point")
      (libsource (lib "") (part "Test_point_1"))
    )
    (comp (ref "Tp13")
      (value "PC12-LC3")
      (footprint "TEST_POINT_THD_D1.8MM")
      (description "Test point")
      (libsource (lib "") (part "Test_point_1"))
    )
    (comp (ref "Tp14")
      (value "PB5-KC4")
      (footprint "TEST_POINT_THD_D1.8MM")
      (description "Test point")
      (libsource (lib "") (part "Test_point_1"))
    )
    (comp (ref "Tp15")
      (value "PC13-LC4")
      (footprint "TEST_POINT_THD_D1.8MM")
      (description "Test point")
      (libsource (lib "") (part "Test_point_1"))
    )
    (comp (ref "Tp16")
      (value "PB6-KC5")
      (footprint "TEST_POINT_THD_D1.8MM")
      (description "Test point")
      (libsource (lib "") (part "Test_point_1"))
    )
    (comp (ref "Tp17")
      (value "PC14-LC5")
      (footprint "TEST_POINT_THD_D1.8MM")
      (description "Test point")
      (libsource (lib "") (part "Test_point_1"))
    )
    (comp (ref "Tp18")
      (value "PB7-KC6")
      (footprint "TEST_POINT_THD_D1.8MM")
      (description "Test point")
      (libsource (lib "") (part "Test_point_1"))
    )
    (comp (ref "Tp19")
      (value "PC15-LC6")
      (footprint "TEST_POINT_THD_D1.8MM")
      (description "Test point")
      (libsource (lib "") (part "Test_point_1"))
    )
    (comp (ref "Tp20")
      (value "PB8-KC7")
      (footprint "TEST_POINT_THD_D1.8MM")
      (description "Test point")
      (libsource (lib "") (part "Test_point_1"))
    )
    (comp (ref "Tp21")
      (value "PB15-LC7")
      (footprint "TEST_POINT_THD_D1.8MM")
      (description "Test point")
      (libsource (lib "") (part "Test_point_1"))
    )
    (comp (ref "Tp22")
      (value "PB9-KC8")
      (footprint "TEST_POINT_THD_D1.8MM")
      (description "Test point")
      (libsource (lib "") (part "Test_point_1"))
    )
    (comp (ref "Tp23")
      (value "PB12-KC9")
      (footprint "TEST_POINT_THD_D1.8MM")
      (description "Test point")
      (libsource (lib "") (part "Test_point_1"))
    )
    (comp (ref "Tp24")
      (value "PB13-KC10")
      (footprint "TEST_POINT_THD_D1.8MM")
      (description "Test point")
      (libsource (lib "") (part "Test_point_1"))
    )
    (comp (ref "Tp25")
      (value "PB14-KC11")
      (footprint "TEST_POINT_THD_D1.8MM")
      (description "Test point")
      (libsource (lib "") (part "Test_point_1"))
    )
    (comp (ref "Tp26")
      (value "PC0-LR0")
      (footprint "TEST_POINT_THD_D1.8MM")
      (description "Test point")
      (libsource (lib "DEVELER_Library") (part "Test_point"))
    )
    (comp (ref "Tp27")
      (value "PA0-KR0")
      (footprint "TEST_POINT_THD_D1.8MM")
      (description "Test point")
      (libsource (lib "DEVELER_Library") (part "Test_point"))
    )
    (comp (ref "Tp28")
      (value "PC1-LR1")
      (footprint "TEST_POINT_THD_D1.8MM")
      (description "Test point")
      (libsource (lib "DEVELER_Library") (part "Test_point"))
    )
    (comp (ref "Tp29")
      (value "PA1-KR1")
      (footprint "TEST_POINT_THD_D1.8MM")
      (description "Test point")
      (libsource (lib "DEVELER_Library") (part "Test_point"))
    )
    (comp (ref "Tp30")
      (value "PC2-LR2")
      (footprint "TEST_POINT_THD_D1.8MM")
      (description "Test point")
      (libsource (lib "DEVELER_Library") (part "Test_point"))
    )
    (comp (ref "Tp31")
      (value "PA4-KR2")
      (footprint "TEST_POINT_THD_D1.8MM")
      (description "Test point")
      (libsource (lib "DEVELER_Library") (part "Test_point"))
    )
    (comp (ref "Tp32")
      (value "PC3-LR3")
      (footprint "TEST_POINT_THD_D1.8MM")
      (description "Test point")
      (libsource (lib "DEVELER_Library") (part "Test_point"))
    )
    (comp (ref "Tp33")
      (value "PA5-KR3")
      (footprint "TEST_POINT_THD_D1.8MM")
      (description "Test point")
      (libsource (lib "DEVELER_Library") (part "Test_point"))
    )
    (comp (ref "Tp34")
      (value "PC4-LR4")
      (footprint "TEST_POINT_THD_D1.8MM")
      (description "Test point")
      (libsource (lib "DEVELER_Library") (part "Test_point"))
    )
    (comp (ref "Tp35")
      (value "PA6-KR4")
      (footprint "TEST_POINT_THD_D1.8MM")
      (description "Test point")
      (libsource (lib "DEVELER_Library") (part "Test_point"))
    )
    (comp (ref "Tp36")
      (value "PC5-LR5")
      (footprint "TEST_POINT_THD_D1.8MM")
      (description "Test point")
      (libsource (lib "DEVELER_Library") (part "Test_point"))
    )
    (comp (ref "Tp37")
      (value "PA7-KR5")
      (footprint "TEST_POINT_THD_D1.8MM")
      (description "Test point")
      (libsource (lib "DEVELER_Library") (part "Test_point"))
    )
    (comp (ref "Tp38")
      (value "PC6-LR6")
      (footprint "TEST_POINT_THD_D1.8MM")
      (description "Test point")
      (libsource (lib "DEVELER_Library") (part "Test_point"))
    )
    (comp (ref "Tp39")
      (value "PA8-KR6")
      (footprint "TEST_POINT_THD_D1.8MM")
      (description "Test point")
      (libsource (lib "DEVELER_Library") (part "Test_point"))
    )
    (comp (ref "Tp40")
      (value "PC7-LR7")
      (footprint "TEST_POINT_THD_D1.8MM")
      (description "Test point")
      (libsource (lib "DEVELER_Library") (part "Test_point"))
    )
    (comp (ref "Tp41")
      (value "PA9-KR7")
      (footprint "TEST_POINT_THD_D1.8MM")
      (description "Test point")
      (libsource (lib "DEVELER_Library") (part "Test_point"))
    )
    (comp (ref "Tp42")
      (value "PA10-KR8")
      (footprint "TEST_POINT_THD_D1.8MM")
      (description "Test point")
      (libsource (lib "DEVELER_Library") (part "Test_point"))
    )
    (comp (ref "Tp43")
      (value "PA13-KR9")
      (footprint "TEST_POINT_THD_D1.8MM")
      (description "Test point")
      (libsource (lib "DEVELER_Library") (part "Test_point"))
    )
    (comp (ref "Tp44")
      (value "PA14-KR10")
      (footprint "TEST_POINT_THD_D1.8MM")
      (description "Test point")
      (libsource (lib "DEVELER_Library") (part "Test_point"))
    )
    (comp (ref "Tp45")
      (value "PA15-KR11")
      (footprint "TEST_POINT_THD_D1.8MM")
      (description "Test point")
      (libsource (lib "DEVELER_Library") (part "Test_point"))
    )
  )
  (nets
    (net (code "1") (name "/PA0") (class "Default")
      (node (ref "C32") (pin "1") (pinfunction "1_1") (pintype "passive"))
      (node (ref "R35") (pin "1") (pinfunction "1_1") (pintype "passive"))
      (node (ref "Tp27") (pin "1") (pinfunction "1_1") (pintype "passive"))
    )
    (net (code "2") (name "/PA1") (class "Default")
      (node (ref "C33") (pin "1") (pinfunction "1_1") (pintype "passive"))
      (node (ref "R37") (pin "1") (pinfunction "1_1") (pintype "passive"))
      (node (ref "Tp29") (pin "1") (pinfunction "1_1") (pintype "passive"))
    )
    (net (code "3") (name "/PA4") (class "Default")
      (node (ref "C34") (pin "1") (pinfunction "1_1") (pintype "passive"))
      (node (ref "R39") (pin "1") (pinfunction "1_1") (pintype "passive"))
      (node (ref "Tp31") (pin "1") (pinfunction "1_1") (pintype "passive"))
    )
    (net (code "4") (name "/PA5") (class "Default")
      (node (ref "C35") (pin "1") (pinfunction "1_1") (pintype "passive"))
      (node (ref "R41") (pin "1") (pinfunction "1_1") (pintype "passive"))
      (node (ref "Tp33") (pin "1") (pinfunction "1_1") (pintype "passive"))
    )
    (net (code "5") (name "/PA6") (class "Default")
      (node (ref "C36") (pin "1") (pinfunction "1_1") (pintype "passive"))
      (node (ref "R43") (pin "1") (pinfunction "1_1") (pintype "passive"))
      (node (ref "Tp35") (pin "1") (pinfunction "1_1") (pintype "passive"))
    )
    (net (code "6") (name "/PA7") (class "Default")
      (node (ref "C37") (pin "1") (pinfunction "1_1") (pintype "passive"))
      (node (ref "R45") (pin "1") (pinfunction "1_1") (pintype "passive"))
      (node (ref "Tp37") (pin "1") (pinfunction "1_1") (pintype "passive"))
    )
    (net (code "7") (name "/PA8") (class "Default")
      (node (ref "C38") (pin "1") (pinfunction "1_1") (pintype "passive"))
      (node (ref "R47") (pin "1") (pinfunction "1_1") (pintype "passive"))
      (node (ref "Tp39") (pin "1") (pinfunction "1_1") (pintype "passive"))
    )
    (net (code "8") (name "/PA9") (class "Default")
      (node (ref "C39") (pin "1") (pinfunction "1_1") (pintype "passive"))
      (node (ref "R49") (pin "1") (pinfunction "1_1") (pintype "passive"))
      (node (ref "Tp41") (pin "1") (pinfunction "1_1") (pintype "passive"))
    )
    (net (code "9") (name "/PA10") (class "Default")
      (node (ref "C40") (pin "1") (pinfunction "1_1") (pintype "passive"))
      (node (ref "R50") (pin "1") (pinfunction "1_1") (pintype "passive"))
      (node (ref "Tp42") (pin "1") (pinfunction "1_1") (pintype "passive"))
    )
    (net (code "10") (name "/PA13") (class "Default")
      (node (ref "C41") (pin "1") (pinfunction "1_1") (pintype "passive"))
      (node (ref "R51") (pin "1") (pinfunction "1_1") (pintype "passive"))
      (node (ref "Tp43") (pin "1") (pinfunction "1_1") (pintype "passive"))
    )
    (net (code "11") (name "/PA14") (class "Default")
      (node (ref "C42") (pin "1") (pinfunction "1_1") (pintype "passive"))
      (node (ref "R52") (pin "1") (pinfunction "1_1") (pintype "passive"))
      (node (ref "Tp44") (pin "1") (pinfunction "1_1") (pintype "passive"))
    )
    (net (code "12") (name "/PA15") (class "Default")
      (node (ref "C43") (pin "1") (pinfunction "1_1") (pintype "passive"))
      (node (ref "R53") (pin "1") (pinfunction "1_1") (pintype "passive"))
      (node (ref "Tp45") (pin "1") (pinfunction "1_1") (pintype "passive"))
    )
    (net (code "13") (name "/PB0") (class "Default")
      (node (ref "C20") (pin "1") (pinfunction "1_1") (pintype "passive"))
      (node (ref "R22") (pin "1") (pinfunction "1_1") (pintype "passive"))
      (node (ref "Tp6") (pin "1") (pinfunction "1_1") (pintype "passive"))
    )
    (net (code "14") (name "/PB1") (class "Default")
      (node (ref "C21") (pin "1") (pinfunction "1_1") (pintype "passive"))
      (node (ref "R23") (pin "1") (pinfunction "1_1") (pintype "passive"))
      (node (ref "Tp8") (pin "1") (pinfunction "1_1") (pintype "passive"))
    )
    (net (code "15") (name "/PB3") (class "Default")
      (node (ref "C22") (pin "1") (pinfunction "1_1") (pintype "passive"))
      (node (ref "R24") (pin "1") (pinfunction "1_1") (pintype "passive"))
      (node (ref "Tp10") (pin "1") (pinfunction "1_1") (pintype "passive"))
    )
    (net (code "16") (name "/PB4") (class "Default")
      (node (ref "C23") (pin "1") (pinfunction "1_1") (pintype "passive"))
      (node (ref "R25") (pin "1") (pinfunction "1_1") (pintype "passive"))
      (node (ref "Tp12") (pin "1") (pinfunction "1_1") (pintype "passive"))
    )
    (net (code "17") (name "/PB5") (class "Default")
      (node (ref "C24") (pin "1") (pinfunction "1_1") (pintype "passive"))
      (node (ref "R26") (pin "1") (pinfunction "1_1") (pintype "passive"))
      (node (ref "Tp14") (pin "1") (pinfunction "1_1") (pintype "passive"))
    )
    (net (code "18") (name "/PB6") (class "Default")
      (node (ref "C25") (pin "1") (pinfunction "1_1") (pintype "passive"))
      (node (ref "R27") (pin "1") (pinfunction "1_1") (pintype "passive"))
      (node (ref "Tp16") (pin "1") (pinfunction "1_1") (pintype "passive"))
    )
    (net (code "19") (name "/PB7") (class "Default")
      (node (ref "C26") (pin "1") (pinfunction "1_1") (pintype "passive"))
      (node (ref "R28") (pin "1") (pinfunction "1_1") (pintype "passive"))
      (node (ref "Tp18") (pin "1") (pinfunction "1_1") (pintype "passive"))
    )
    (net (code "20") (name "/PB8") (class "Default")
      (node (ref "C27") (pin "1") (pinfunction "1_1") (pintype "passive"))
      (node (ref "R29") (pin "1") (pinfunction "1_1") (pintype "passive"))
      (node (ref "Tp20") (pin "1") (pinfunction "1_1") (pintype "passive"))
    )
    (net (code "21") (name "/PB9") (class "Default")
      (node (ref "C28") (pin "1") (pinfunction "1_1") (pintype "passive"))
      (node (ref "R30") (pin "1") (pinfunction "1_1") (pintype "passive"))
      (node (ref "Tp22") (pin "1") (pinfunction "1_1") (pintype "passive"))
    )
    (net (code "22") (name "/PB12") (class "Default")
      (node (ref "C29") (pin "1") (pinfunction "1_1") (pintype "passive"))
      (node (ref "R31") (pin "1") (pinfunction "1_1") (pintype "passive"))
      (node (ref "Tp23") (pin "1") (pinfunction "1_1") (pintype "passive"))
    )
    (net (code "23") (name "/PB13") (class "Default")
      (node (ref "C30") (pin "1") (pinfunction "1_1") (pintype "passive"))
      (node (ref "R32") (pin "1") (pinfunction "1_1") (pintype "passive"))
      (node (ref "Tp24") (pin "1") (pinfunction "1_1") (pintype "passive"))
    )
    (net (code "24") (name "/PB14") (class "Default")
      (node (ref "C31") (pin "1") (pinfunction "1_1") (pintype "passive"))
      (node (ref "R33") (pin "1") (pinfunction "1_1") (pintype "passive"))
      (node (ref "Tp25") (pin "1") (pinfunction "1_1") (pintype "passive"))
    )
    (net (code "25") (name "/PB15") (class "Default")
      (node (ref "K104") (pin "2") (pinfunction "2_2") (pintype "passive"))
      (node (ref "K116") (pin "2") (pinfunction "2_2") (pintype "passive"))
      (node (ref "K128") (pin "2") (pinfunction "2_2") (pintype "passive"))
      (node (ref "K140") (pin "2") (pinfunction "2_2") (pintype "passive"))
      (node (ref "K20") (pin "2") (pinfunction "2_2") (pintype "passive"))
      (node (ref "K32") (pin "2") (pinfunction "2_2") (pintype "passive"))
      (node (ref "K44") (pin "2") (pinfunction "2_2") (pintype "passive"))
      (node (ref "K56") (pin "2") (pinfunction "2_2") (pintype "passive"))
      (node (ref "K68") (pin "2") (pinfunction "2_2") (pintype "passive"))
      (node (ref "K8") (pin "2") (pinfunction "2_2") (pintype "passive"))
      (node (ref "K80") (pin "2") (pinfunction "2_2") (pintype "passive"))
      (node (ref "K92") (pin "2") (pinfunction "2_2") (pintype "passive"))
      (node (ref "Tp21") (pin "1") (pinfunction "1_1") (pintype "passive"))
    )
    (net (code "26") (name "/PC0") (class "Default")
      (node (ref "R34") (pin "1") (pinfunction "1_1") (pintype "passive"))
      (node (ref "Tp26") (pin "1") (pinfunction "1_1") (pintype "passive"))
    )
    (net (code "27") (name "/PC1") (class "Default")
      (node (ref "R36") (pin "1") (pinfunction "1_1") (pintype "passive"))
      (node (ref "Tp28") (pin "1") (pinfunction "1_1") (pintype "passive"))
    )
    (net (code "28") (name "/PC2") (class "Default")
      (node (ref "R38") (pin "1") (pinfunction "1_1") (pintype "passive"))
      (node (ref "Tp30") (pin "1") (pinfunction "1_1") (pintype "passive"))
    )
    (net (code "29") (name "/PC3") (class "Default")
      (node (ref "R40") (pin "1") (pinfunction "1_1") (pintype "passive"))
      (node (ref "Tp32") (pin "1") (pinfunction "1_1") (pintype "passive"))
    )
    (net (code "30") (name "/PC4") (class "Default")
      (node (ref "R42") (pin "1") (pinfunction "1_1") (pintype "passive"))
      (node (ref "Tp34") (pin "1") (pinfunction "1_1") (pintype "passive"))
    )
    (net (code "31") (name "/PC5") (class "Default")
      (node (ref "R44") (pin "1") (pinfunction "1_1") (pintype "passive"))
      (node (ref "Tp36") (pin "1") (pinfunction "1_1") (pintype "passive"))
    )
    (net (code "32") (name "/PC6") (class "Default")
      (node (ref "R46") (pin "1") (pinfunction "1_1") (pintype "passive"))
      (node (ref "Tp38") (pin "1") (pinfunction "1_1") (pintype "passive"))
    )
    (net (code "33") (name "/PC7") (class "Default")
      (node (ref "R48") (pin "1") (pinfunction "1_1") (pintype "passive"))
      (node (ref "Tp40") (pin "1") (pinfunction "1_1") (pintype "passive"))
    )
    (net (code "34") (name "/PC8") (class "Default")
      (node (ref "K1") (pin "2") (pinfunction "2_2") (pintype "passive"))
      (node (ref "K109") (pin "2") (pinfunction "2_2") (pintype "passive"))
      (node (ref "K121") (pin "2") (pinfunction "2_2") (pintype "passive"))
      (node (ref "K13") (pin "2") (pinfunction "2_2") (pintype "passive"))
      (node (ref "K133") (pin "2") (pinfunction "2_2") (pintype "passive"))
      (node (ref "K25") (pin "2") (pinfunction "2_2") (pintype "passive"))
      (node (ref "K37") (pin "2") (pinfunction "2_2") (pintype "passive"))
      (node (ref "K49") (pin "2") (pinfunction "2_2") (pintype "passive"))
      (node (ref "K61") (pin "2") (pinfunction "2_2") (pintype "passive"))
      (node (ref "K73") (pin "2") (pinfunction "2_2") (pintype "passive"))
      (node (ref "K85") (pin "2") (pinfunction "2_2") (pintype "passive"))
      (node (ref "K97") (pin "2") (pinfunction "2_2") (pintype "passive"))
      (node (ref "Tp7") (pin "1") (pinfunction "1_1") (pintype "passive"))
    )
    (net (code "35") (name "/PC9") (class "Default")
      (node (ref "K110") (pin "2") (pinfunction "2_2") (pintype "passive"))
      (node (ref "K122") (pin "2") (pinfunction "2_2") (pintype "passive"))
      (node (ref "K134") (pin "2") (pinfunction "2_2") (pintype "passive"))
      (node (ref "K14") (pin "2") (pinfunction "2_2") (pintype "passive"))
      (node (ref "K2") (pin "2") (pinfunction "2_2") (pintype "passive"))
      (node (ref "K26") (pin "2") (pinfunction "2_2") (pintype "passive"))
      (node (ref "K38") (pin "2") (pinfunction "2_2") (pintype "passive"))
      (node (ref "K50") (pin "2") (pinfunction "2_2") (pintype "passive"))
      (node (ref "K62") (pin "2") (pinfunction "2_2") (pintype "passive"))
      (node (ref "K74") (pin "2") (pinfunction "2_2") (pintype "passive"))
      (node (ref "K86") (pin "2") (pinfunction "2_2") (pintype "passive"))
      (node (ref "K98") (pin "2") (pinfunction "2_2") (pintype "passive"))
      (node (ref "Tp9") (pin "1") (pinfunction "1_1") (pintype "passive"))
    )
    (net (code "36") (name "/PC10") (class "Default")
      (node (ref "K111") (pin "2") (pinfunction "2_2") (pintype "passive"))
      (node (ref "K123") (pin "2") (pinfunction "2_2") (pintype "passive"))
      (node (ref "K135") (pin "2") (pinfunction "2_2") (pintype "passive"))
      (node (ref "K15") (pin "2") (pinfunction "2_2") (pintype "passive"))
      (node (ref "K27") (pin "2") (pinfunction "2_2") (pintype "passive"))
      (node (ref "K3") (pin "2") (pinfunction "2_2") (pintype "passive"))
      (node (ref "K39") (pin "2") (pinfunction "2_2") (pintype "passive"))
      (node (ref "K51") (pin "2") (pinfunction "2_2") (pintype "passive"))
      (node (ref "K63") (pin "2") (pinfunction "2_2") (pintype "passive"))
      (node (ref "K75") (pin "2") (pinfunction "2_2") (pintype "passive"))
      (node (ref "K87") (pin "2") (pinfunction "2_2") (pintype "passive"))
      (node (ref "K99") (pin "2") (pinfunction "2_2") (pintype "passive"))
      (node (ref "Tp11") (pin "1") (pinfunction "1_1") (pintype "passive"))
    )
    (net (code "37") (name "/PC12") (class "Default")
      (node (ref "K100") (pin "2") (pinfunction "2_2") (pintype "passive"))
      (node (ref "K112") (pin "2") (pinfunction "2_2") (pintype "passive"))
      (node (ref "K124") (pin "2") (pinfunction "2_2") (pintype "passive"))
      (node (ref "K136") (pin "2") (pinfunction "2_2") (pintype "passive"))
      (node (ref "K16") (pin "2") (pinfunction "2_2") (pintype "passive"))
      (node (ref "K28") (pin "2") (pinfunction "2_2") (pintype "passive"))
      (node (ref "K4") (pin "2") (pinfunction "2_2") (pintype "passive"))
      (node (ref "K40") (pin "2") (pinfunction "2_2") (pintype "passive"))
      (node (ref "K52") (pin "2") (pinfunction "2_2") (pintype "passive"))
      (node (ref "K64") (pin "2") (pinfunction "2_2") (pintype "passive"))
      (node (ref "K76") (pin "2") (pinfunction "2_2") (pintype "passive"))
      (node (ref "K88") (pin "2") (pinfunction "2_2") (pintype "passive"))
      (node (ref "Tp13") (pin "1") (pinfunction "1_1") (pintype "passive"))
    )
    (net (code "38") (name "/PC13") (class "Default")
      (node (ref "K101") (pin "2") (pinfunction "2_2") (pintype "passive"))
      (node (ref "K113") (pin "2") (pinfunction "2_2") (pintype "passive"))
      (node (ref "K125") (pin "2") (pinfunction "2_2") (pintype "passive"))
      (node (ref "K137") (pin "2") (pinfunction "2_2") (pintype "passive"))
      (node (ref "K17") (pin "2") (pinfunction "2_2") (pintype "passive"))
      (node (ref "K29") (pin "2") (pinfunction "2_2") (pintype "passive"))
      (node (ref "K41") (pin "2") (pinfunction "2_2") (pintype "passive"))
      (node (ref "K5") (pin "2") (pinfunction "2_2") (pintype "passive"))
      (node (ref "K53") (pin "2") (pinfunction "2_2") (pintype "passive"))
      (node (ref "K65") (pin "2") (pinfunction "2_2") (pintype "passive"))
      (node (ref "K77") (pin "2") (pinfunction "2_2") (pintype "passive"))
      (node (ref "K89") (pin "2") (pinfunction "2_2") (pintype "passive"))
      (node (ref "Tp15") (pin "1") (pinfunction "1_1") (pintype "passive"))
    )
    (net (code "39") (name "/PC14") (class "Default")
      (node (ref "K102") (pin "2") (pinfunction "2_2") (pintype "passive"))
      (node (ref "K114") (pin "2") (pinfunction "2_2") (pintype "passive"))
      (node (ref "K126") (pin "2") (pinfunction "2_2") (pintype "passive"))
      (node (ref "K138") (pin "2") (pinfunction "2_2") (pintype "passive"))
      (node (ref "K18") (pin "2") (pinfunction "2_2") (pintype "passive"))
      (node (ref "K30") (pin "2") (pinfunction "2_2") (pintype "passive"))
      (node (ref "K42") (pin "2") (pinfunction "2_2") (pintype "passive"))
      (node (ref "K54") (pin "2") (pinfunction "2_2") (pintype "passive"))
      (node (ref "K6") (pin "2") (pinfunction "2_2") (pintype "passive"))
      (node (ref "K66") (pin "2") (pinfunction "2_2") (pintype "passive"))
      (node (ref "K78") (pin "2") (pinfunction "2_2") (pintype "passive"))
      (node (ref "K90") (pin "2") (pinfunction "2_2") (pintype "passive"))
      (node (ref "Tp17") (pin "1") (pinfunction "1_1") (pintype "passive"))
    )
    (net (code "40") (name "/PC15") (class "Default")
      (node (ref "K103") (pin "2") (pinfunction "2_2") (pintype "passive"))
      (node (ref "K115") (pin "2") (pinfunction "2_2") (pintype "passive"))
      (node (ref "K127") (pin "2") (pinfunction "2_2") (pintype "passive"))
      (node (ref "K139") (pin "2") (pinfunction "2_2") (pintype "passive"))
      (node (ref "K19") (pin "2") (pinfunction "2_2") (pintype "passive"))
      (node (ref "K31") (pin "2") (pinfunction "2_2") (pintype "passive"))
      (node (ref "K43") (pin "2") (pinfunction "2_2") (pintype "passive"))
      (node (ref "K55") (pin "2") (pinfunction "2_2") (pintype "passive"))
      (node (ref "K67") (pin "2") (pinfunction "2_2") (pintype "passive"))
      (node (ref "K7") (pin "2") (pinfunction "2_2") (pintype "passive"))
      (node (ref "K79") (pin "2") (pinfunction "2_2") (pintype "passive"))
      (node (ref "K91") (pin "2") (pinfunction "2_2") (pintype "passive"))
      (node (ref "Tp19") (pin "1") (pinfunction "1_1") (pintype "passive"))
    )
    (net (code "41") (name "Net-(C20-Pad2)") (class "Default")
      (node (ref "C20") (pin "2") (pinfunction "2_2") (pintype "passive"))
      (node (ref "K1") (pin "3") (pinfunction "3_3") (pintype "passive"))
      (node (ref "K109") (pin "3") (pinfunction "3_3") (pintype "passive"))
      (node (ref "K121") (pin "3") (pinfunction "3_3") (pintype "passive"))
      (node (ref "K13") (pin "3") (pinfunction "3_3") (pintype "passive"))
      (node (ref "K133") (pin "3") (pinfunction "3_3") (pintype "passive"))
      (node (ref "K25") (pin "3") (pinfunction "3_3") (pintype "passive"))
      (node (ref "K37") (pin "3") (pinfunction "3_3") (pintype "passive"))
      (node (ref "K49") (pin "3") (pinfunction "3_3") (pintype "passive"))
      (node (ref "K61") (pin "3") (pinfunction "3_3") (pintype "passive"))
      (node (ref "K73") (pin "3") (pinfunction "3_3") (pintype "passive"))
      (node (ref "K85") (pin "3") (pinfunction "3_3") (pintype "passive"))
      (node (ref "K97") (pin "3") (pinfunction "3_3") (pintype "passive"))
      (node (ref "R22") (pin "2") (pinfunction "2_2") (pintype "passive"))
    )
    (net (code "42") (name "Net-(C21-Pad2)") (class "Default")
      (node (ref "C21") (pin "2") (pinfunction "2_2") (pintype "passive"))
      (node (ref "K110") (pin "3") (pinfunction "3_3") (pintype "passive"))
      (node (ref "K122") (pin "3") (pinfunction "3_3") (pintype "passive"))
      (node (ref "K134") (pin "3") (pinfunction "3_3") (pintype "passive"))
      (node (ref "K14") (pin "3") (pinfunction "3_3") (pintype "passive"))
      (node (ref "K2") (pin "3") (pinfunction "3_3") (pintype "passive"))
      (node (ref "K26") (pin "3") (pinfunction "3_3") (pintype "passive"))
      (node (ref "K38") (pin "3") (pinfunction "3_3") (pintype "passive"))
      (node (ref "K50") (pin "3") (pinfunction "3_3") (pintype "passive"))
      (node (ref "K62") (pin "3") (pinfunction "3_3") (pintype "passive"))
      (node (ref "K74") (pin "3") (pinfunction "3_3") (pintype "passive"))
      (node (ref "K86") (pin "3") (pinfunction "3_3") (pintype "passive"))
      (node (ref "K98") (pin "3") (pinfunction "3_3") (pintype "passive"))
      (node (ref "R23") (pin "2") (pinfunction "2_2") (pintype "passive"))
    )
    (net (code "43") (name "Net-(C22-Pad2)") (class "Default")
      (node (ref "C22") (pin "2") (pinfunction "2_2") (pintype "passive"))
      (node (ref "K111") (pin "3") (pinfunction "3_3") (pintype "passive"))
      (node (ref "K123") (pin "3") (pinfunction "3_3") (pintype "passive"))
      (node (ref "K135") (pin "3") (pinfunction "3_3") (pintype "passive"))
      (node (ref "K15") (pin "3") (pinfunction "3_3") (pintype "passive"))
      (node (ref "K27") (pin "3") (pinfunction "3_3") (pintype "passive"))
      (node (ref "K3") (pin "3") (pinfunction "3_3") (pintype "passive"))
      (node (ref "K39") (pin "3") (pinfunction "3_3") (pintype "passive"))
      (node (ref "K51") (pin "3") (pinfunction "3_3") (pintype "passive"))
      (node (ref "K63") (pin "3") (pinfunction "3_3") (pintype "passive"))
      (node (ref "K75") (pin "3") (pinfunction "3_3") (pintype "passive"))
      (node (ref "K87") (pin "3") (pinfunction "3_3") (pintype "passive"))
      (node (ref "K99") (pin "3") (pinfunction "3_3") (pintype "passive"))
      (node (ref "R24") (pin "2") (pinfunction "2_2") (pintype "passive"))
    )
    (net (code "44") (name "Net-(C23-Pad2)") (class "Default")
      (node (ref "C23") (pin "2") (pinfunction "2_2") (pintype "passive"))
      (node (ref "K100") (pin "3") (pinfunction "3_3") (pintype "passive"))
      (node (ref "K112") (pin "3") (pinfunction "3_3") (pintype "passive"))
      (node (ref "K124") (pin "3") (pinfunction "3_3") (pintype "passive"))
      (node (ref "K136") (pin "3") (pinfunction "3_3") (pintype "passive"))
      (node (ref "K16") (pin "3") (pinfunction "3_3") (pintype "passive"))
      (node (ref "K28") (pin "3") (pinfunction "3_3") (pintype "passive"))
      (node (ref "K4") (pin "3") (pinfunction "3_3") (pintype "passive"))
      (node (ref "K40") (pin "3") (pinfunction "3_3") (pintype "passive"))
      (node (ref "K52") (pin "3") (pinfunction "3_3") (pintype "passive"))
      (node (ref "K64") (pin "3") (pinfunction "3_3") (pintype "passive"))
      (node (ref "K76") (pin "3") (pinfunction "3_3") (pintype "passive"))
      (node (ref "K88") (pin "3") (pinfunction "3_3") (pintype "passive"))
      (node (ref "R25") (pin "2") (pinfunction "2_2") (pintype "passive"))
    )
    (net (code "45") (name "Net-(C24-Pad2)") (class "Default")
      (node (ref "C24") (pin "2") (pinfunction "2_2") (pintype "passive"))
      (node (ref "K101") (pin "3") (pinfunction "3_3") (pintype "passive"))
      (node (ref "K113") (pin "3") (pinfunction "3_3") (pintype "passive"))
      (node (ref "K125") (pin "3") (pinfunction "3_3") (pintype "passive"))
      (node (ref "K137") (pin "3") (pinfunction "3_3") (pintype "passive"))
      (node (ref "K17") (pin "3") (pinfunction "3_3") (pintype "passive"))
      (node (ref "K29") (pin "3") (pinfunction "3_3") (pintype "passive"))
      (node (ref "K41") (pin "3") (pinfunction "3_3") (pintype "passive"))
      (node (ref "K5") (pin "3") (pinfunction "3_3") (pintype "passive"))
      (node (ref "K53") (pin "3") (pinfunction "3_3") (pintype "passive"))
      (node (ref "K65") (pin "3") (pinfunction "3_3") (pintype "passive"))
      (node (ref "K77") (pin "3") (pinfunction "3_3") (pintype "passive"))
      (node (ref "K89") (pin "3") (pinfunction "3_3") (pintype "passive"))
      (node (ref "R26") (pin "2") (pinfunction "2_2") (pintype "passive"))
    )
    (net (code "46") (name "Net-(C25-Pad2)") (class "Default")
      (node (ref "C25") (pin "2") (pinfunction "2_2") (pintype "passive"))
      (node (ref "K102") (pin "3") (pinfunction "3_3") (pintype "passive"))
      (node (ref "K114") (pin "3") (pinfunction "3_3") (pintype "passive"))
      (node (ref "K126") (pin "3") (pinfunction "3_3") (pintype "passive"))
      (node (ref "K138") (pin "3") (pinfunction "3_3") (pintype "passive"))
      (node (ref "K18") (pin "3") (pinfunction "3_3") (pintype "passive"))
      (node (ref "K30") (pin "3") (pinfunction "3_3") (pintype "passive"))
      (node (ref "K42") (pin "3") (pinfunction "3_3") (pintype "passive"))
      (node (ref "K54") (pin "3") (pinfunction "3_3") (pintype "passive"))
      (node (ref "K6") (pin "3") (pinfunction "3_3") (pintype "passive"))
      (node (ref "K66") (pin "3") (pinfunction "3_3") (pintype "passive"))
      (node (ref "K78") (pin "3") (pinfunction "3_3") (pintype "passive"))
      (node (ref "K90") (pin "3") (pinfunction "3_3") (pintype "passive"))
      (node (ref "R27") (pin "2") (pinfunction "2_2") (pintype "passive"))
    )
    (net (code "47") (name "Net-(C26-Pad2)") (class "Default")
      (node (ref "C26") (pin "2") (pinfunction "2_2") (pintype "passive"))
      (node (ref "K103") (pin "3") (pinfunction "3_3") (pintype "passive"))
      (node (ref "K115") (pin "3") (pinfunction "3_3") (pintype "passive"))
      (node (ref "K127") (pin "3") (pinfunction "3_3") (pintype "passive"))
      (node (ref "K139") (pin "3") (pinfunction "3_3") (pintype "passive"))
      (node (ref "K19") (pin "3") (pinfunction "3_3") (pintype "passive"))
      (node (ref "K31") (pin "3") (pinfunction "3_3") (pintype "passive"))
      (node (ref "K43") (pin "3") (pinfunction "3_3") (pintype "passive"))
      (node (ref "K55") (pin "3") (pinfunction "3_3") (pintype "passive"))
      (node (ref "K67") (pin "3") (pinfunction "3_3") (pintype "passive"))
      (node (ref "K7") (pin "3") (pinfunction "3_3") (pintype "passive"))
      (node (ref "K79") (pin "3") (pinfunction "3_3") (pintype "passive"))
      (node (ref "K91") (pin "3") (pinfunction "3_3") (pintype "passive"))
      (node (ref "R28") (pin "2") (pinfunction "2_2") (pintype "passive"))
    )
    (net (code "48") (name "Net-(C27-Pad2)") (class "Default")
      (node (ref "C27") (pin "2") (pinfunction "2_2") (pintype "passive"))
      (node (ref "K104") (pin "3") (pinfunction "3_3") (pintype "passive"))
      (node (ref "K116") (pin "3") (pinfunction "3_3") (pintype "passive"))
      (node (ref "K128") (pin "3") (pinfunction "3_3") (pintype "passive"))
      (node (ref "K140") (pin "3") (pinfunction "3_3") (pintype "passive"))
      (node (ref "K20") (pin "3") (pinfunction "3_3") (pintype "passive"))
      (node (ref "K32") (pin "3") (pinfunction "3_3") (pintype "passive"))
      (node (ref "K44") (pin "3") (pinfunction "3_3") (pintype "passive"))
      (node (ref "K56") (pin "3") (pinfunction "3_3") (pintype "passive"))
      (node (ref "K68") (pin "3") (pinfunction "3_3") (pintype "passive"))
      (node (ref "K8") (pin "3") (pinfunction "3_3") (pintype "passive"))
      (node (ref "K80") (pin "3") (pinfunction "3_3") (pintype "passive"))
      (node (ref "K92") (pin "3") (pinfunction "3_3") (pintype "passive"))
      (node (ref "R29") (pin "2") (pinfunction "2_2") (pintype "passive"))
    )
    (net (code "49") (name "Net-(C28-Pad2)") (class "Default")
      (node (ref "C28") (pin "2") (pinfunction "2_2") (pintype "passive"))
      (node (ref "K105") (pin "3") (pinfunction "3_3") (pintype "passive"))
      (node (ref "K117") (pin "3") (pinfunction "3_3") (pintype "passive"))
      (node (ref "K129") (pin "3") (pinfunction "3_3") (pintype "passive"))
      (node (ref "K141") (pin "3") (pinfunction "3_3") (pintype "passive"))
      (node (ref "K21") (pin "3") (pinfunction "3_3") (pintype "passive"))
      (node (ref "K33") (pin "3") (pinfunction "3_3") (pintype "passive"))
      (node (ref "K45") (pin "3") (pinfunction "3_3") (pintype "passive"))
      (node (ref "K57") (pin "3") (pinfunction "3_3") (pintype "passive"))
      (node (ref "K69") (pin "3") (pinfunction "3_3") (pintype "passive"))
      (node (ref "K81") (pin "3") (pinfunction "3_3") (pintype "passive"))
      (node (ref "K9") (pin "3") (pinfunction "3_3") (pintype "passive"))
      (node (ref "K93") (pin "3") (pinfunction "3_3") (pintype "passive"))
      (node (ref "R30") (pin "2") (pinfunction "2_2") (pintype "passive"))
    )
    (net (code "50") (name "Net-(C29-Pad2)") (class "Default")
      (node (ref "C29") (pin "2") (pinfunction "2_2") (pintype "passive"))
      (node (ref "K10") (pin "3") (pinfunction "3_3") (pintype "passive"))
      (node (ref "K106") (pin "3") (pinfunction "3_3") (pintype "passive"))
      (node (ref "K118") (pin "3") (pinfunction "3_3") (pintype "passive"))
      (node (ref "K130") (pin "3") (pinfunction "3_3") (pintype "passive"))
      (node (ref "K142") (pin "3") (pinfunction "3_3") (pintype "passive"))
      (node (ref "K22") (pin "3") (pinfunction "3_3") (pintype "passive"))
      (node (ref "K34") (pin "3") (pinfunction "3_3") (pintype "passive"))
      (node (ref "K46") (pin "3") (pinfunction "3_3") (pintype "passive"))
      (node (ref "K58") (pin "3") (pinfunction "3_3") (pintype "passive"))
      (node (ref "K70") (pin "3") (pinfunction "3_3") (pintype "passive"))
      (node (ref "K82") (pin "3") (pinfunction "3_3") (pintype "passive"))
      (node (ref "K94") (pin "3") (pinfunction "3_3") (pintype "passive"))
      (node (ref "R31") (pin "2") (pinfunction "2_2") (pintype "passive"))
    )
    (net (code "51") (name "Net-(C30-Pad2)") (class "Default")
      (node (ref "C30") (pin "2") (pinfunction "2_2") (pintype "passive"))
      (node (ref "K107") (pin "3") (pinfunction "3_3") (pintype "passive"))
      (node (ref "K11") (pin "3") (pinfunction "3_3") (pintype "passive"))
      (node (ref "K119") (pin "3") (pinfunction "3_3") (pintype "passive"))
      (node (ref "K131") (pin "3") (pinfunction "3_3") (pintype "passive"))
      (node (ref "K143") (pin "3") (pinfunction "3_3") (pintype "passive"))
      (node (ref "K23") (pin "3") (pinfunction "3_3") (pintype "passive"))
      (node (ref "K35") (pin "3") (pinfunction "3_3") (pintype "passive"))
      (node (ref "K47") (pin "3") (pinfunction "3_3") (pintype "passive"))
      (node (ref "K59") (pin "3") (pinfunction "3_3") (pintype "passive"))
      (node (ref "K71") (pin "3") (pinfunction "3_3") (pintype "passive"))
      (node (ref "K83") (pin "3") (pinfunction "3_3") (pintype "passive"))
      (node (ref "K95") (pin "3") (pinfunction "3_3") (pintype "passive"))
      (node (ref "R32") (pin "2") (pinfunction "2_2") (pintype "passive"))
    )
    (net (code "52") (name "Net-(C31-Pad2)") (class "Default")
      (node (ref "C31") (pin "2") (pinfunction "2_2") (pintype "passive"))
      (node (ref "K108") (pin "3") (pinfunction "3_3") (pintype "passive"))
      (node (ref "K12") (pin "3") (pinfunction "3_3") (pintype "passive"))
      (node (ref "K120") (pin "3") (pinfunction "3_3") (pintype "passive"))
      (node (ref "K132") (pin "3") (pinfunction "3_3") (pintype "passive"))
      (node (ref "K144") (pin "3") (pinfunction "3_3") (pintype "passive"))
      (node (ref "K24") (pin "3") (pinfunction "3_3") (pintype "passive"))
      (node (ref "K36") (pin "3") (pinfunction "3_3") (pintype "passive"))
      (node (ref "K48") (pin "3") (pinfunction "3_3") (pintype "passive"))
      (node (ref "K60") (pin "3") (pinfunction "3_3") (pintype "passive"))
      (node (ref "K72") (pin "3") (pinfunction "3_3") (pintype "passive"))
      (node (ref "K84") (pin "3") (pinfunction "3_3") (pintype "passive"))
      (node (ref "K96") (pin "3") (pinfunction "3_3") (pintype "passive"))
      (node (ref "R33") (pin "2") (pinfunction "2_2") (pintype "passive"))
    )
    (net (code "53") (name "Net-(C32-Pad2)") (class "Default")
      (node (ref "C32") (pin "2") (pinfunction "2_2") (pintype "passive"))
      (node (ref "K1") (pin "4") (pinfunction "4_4") (pintype "passive"))
      (node (ref "K10") (pin "4") (pinfunction "4_4") (pintype "passive"))
      (node (ref "K11") (pin "4") (pinfunction "4_4") (pintype "passive"))
      (node (ref "K12") (pin "4") (pinfunction "4_4") (pintype "passive"))
      (node (ref "K2") (pin "4") (pinfunction "4_4") (pintype "passive"))
      (node (ref "K3") (pin "4") (pinfunction "4_4") (pintype "passive"))
      (node (ref "K4") (pin "4") (pinfunction "4_4") (pintype "passive"))
      (node (ref "K5") (pin "4") (pinfunction "4_4") (pintype "passive"))
      (node (ref "K6") (pin "4") (pinfunction "4_4") (pintype "passive"))
      (node (ref "K7") (pin "4") (pinfunction "4_4") (pintype "passive"))
      (node (ref "K8") (pin "4") (pinfunction "4_4") (pintype "passive"))
      (node (ref "K9") (pin "4") (pinfunction "4_4") (pintype "passive"))
      (node (ref "R35") (pin "2") (pinfunction "2_2") (pintype "passive"))
    )
    (net (code "54") (name "Net-(C33-Pad2)") (class "Default")
      (node (ref "C33") (pin "2") (pinfunction "2_2") (pintype "passive"))
      (node (ref "K13") (pin "4") (pinfunction "4_4") (pintype "passive"))
      (node (ref "K14") (pin "4") (pinfunction "4_4") (pintype "passive"))
      (node (ref "K15") (pin "4") (pinfunction "4_4") (pintype "passive"))
      (node (ref "K16") (pin "4") (pinfunction "4_4") (pintype "passive"))
      (node (ref "K17") (pin "4") (pinfunction "4_4") (pintype "passive"))
      (node (ref "K18") (pin "4") (pinfunction "4_4") (pintype "passive"))
      (node (ref "K19") (pin "4") (pinfunction "4_4") (pintype "passive"))
      (node (ref "K20") (pin "4") (pinfunction "4_4") (pintype "passive"))
      (node (ref "K21") (pin "4") (pinfunction "4_4") (pintype "passive"))
      (node (ref "K22") (pin "4") (pinfunction "4_4") (pintype "passive"))
      (node (ref "K23") (pin "4") (pinfunction "4_4") (pintype "passive"))
      (node (ref "K24") (pin "4") (pinfunction "4_4") (pintype "passive"))
      (node (ref "R37") (pin "2") (pinfunction "2_2") (pintype "passive"))
    )
    (net (code "55") (name "Net-(C34-Pad2)") (class "Default")
      (node (ref "C34") (pin "2") (pinfunction "2_2") (pintype "passive"))
      (node (ref "K25") (pin "4") (pinfunction "4_4") (pintype "passive"))
      (node (ref "K26") (pin "4") (pinfunction "4_4") (pintype "passive"))
      (node (ref "K27") (pin "4") (pinfunction "4_4") (pintype "passive"))
      (node (ref "K28") (pin "4") (pinfunction "4_4") (pintype "passive"))
      (node (ref "K29") (pin "4") (pinfunction "4_4") (pintype "passive"))
      (node (ref "K30") (pin "4") (pinfunction "4_4") (pintype "passive"))
      (node (ref "K31") (pin "4") (pinfunction "4_4") (pintype "passive"))
      (node (ref "K32") (pin "4") (pinfunction "4_4") (pintype "passive"))
      (node (ref "K33") (pin "4") (pinfunction "4_4") (pintype "passive"))
      (node (ref "K34") (pin "4") (pinfunction "4_4") (pintype "passive"))
      (node (ref "K35") (pin "4") (pinfunction "4_4") (pintype "passive"))
      (node (ref "K36") (pin "4") (pinfunction "4_4") (pintype "passive"))
      (node (ref "R39") (pin "2") (pinfunction "2_2") (pintype "passive"))
    )
    (net (code "56") (name "Net-(C35-Pad2)") (class "Default")
      (node (ref "C35") (pin "2") (pinfunction "2_2") (pintype "passive"))
      (node (ref "K37") (pin "4") (pinfunction "4_4") (pintype "passive"))
      (node (ref "K38") (pin "4") (pinfunction "4_4") (pintype "passive"))
      (node (ref "K39") (pin "4") (pinfunction "4_4") (pintype "passive"))
      (node (ref "K40") (pin "4") (pinfunction "4_4") (pintype "passive"))
      (node (ref "K41") (pin "4") (pinfunction "4_4") (pintype "passive"))
      (node (ref "K42") (pin "4") (pinfunction "4_4") (pintype "passive"))
      (node (ref "K43") (pin "4") (pinfunction "4_4") (pintype "passive"))
      (node (ref "K44") (pin "4") (pinfunction "4_4") (pintype "passive"))
      (node (ref "K45") (pin "4") (pinfunction "4_4") (pintype "passive"))
      (node (ref "K46") (pin "4") (pinfunction "4_4") (pintype "passive"))
      (node (ref "K47") (pin "4") (pinfunction "4_4") (pintype "passive"))
      (node (ref "K48") (pin "4") (pinfunction "4_4") (pintype "passive"))
      (node (ref "R41") (pin "2") (pinfunction "2_2") (pintype "passive"))
    )
    (net (code "57") (name "Net-(C36-Pad2)") (class "Default")
      (node (ref "C36") (pin "2") (pinfunction "2_2") (pintype "passive"))
      (node (ref "K49") (pin "4") (pinfunction "4_4") (pintype "passive"))
      (node (ref "K50") (pin "4") (pinfunction "4_4") (pintype "passive"))
      (node (ref "K51") (pin "4") (pinfunction "4_4") (pintype "passive"))
      (node (ref "K52") (pin "4") (pinfunction "4_4") (pintype "passive"))
      (node (ref "K53") (pin "4") (pinfunction "4_4") (pintype "passive"))
      (node (ref "K54") (pin "4") (pinfunction "4_4") (pintype "passive"))
      (node (ref "K55") (pin "4") (pinfunction "4_4") (pintype "passive"))
      (node (ref "K56") (pin "4") (pinfunction "4_4") (pintype "passive"))
      (node (ref "K57") (pin "4") (pinfunction "4_4") (pintype "passive"))
      (node (ref "K58") (pin "4") (pinfunction "4_4") (pintype "passive"))
      (node (ref "K59") (pin "4") (pinfunction "4_4") (pintype "passive"))
      (node (ref "K60") (pin "4") (pinfunction "4_4") (pintype "passive"))
      (node (ref "R43") (pin "2") (pinfunction "2_2") (pintype "passive"))
    )
    (net (code "58") (name "Net-(C37-Pad2)") (class "Default")
      (node (ref "C37") (pin "2") (pinfunction "2_2") (pintype "passive"))
      (node (ref "K61") (pin "4") (pinfunction "4_4") (pintype "passive"))
      (node (ref "K62") (pin "4") (pinfunction "4_4") (pintype "passive"))
      (node (ref "K63") (pin "4") (pinfunction "4_4") (pintype "passive"))
      (node (ref "K64") (pin "4") (pinfunction "4_4") (pintype "passive"))
      (node (ref "K65") (pin "4") (pinfunction "4_4") (pintype "passive"))
      (node (ref "K66") (pin "4") (pinfunction "4_4") (pintype "passive"))
      (node (ref "K67") (pin "4") (pinfunction "4_4") (pintype "passive"))
      (node (ref "K68") (pin "4") (pinfunction "4_4") (pintype "passive"))
      (node (ref "K69") (pin "4") (pinfunction "4_4") (pintype "passive"))
      (node (ref "K70") (pin "4") (pinfunction "4_4") (pintype "passive"))
      (node (ref "K71") (pin "4") (pinfunction "4_4") (pintype "passive"))
      (node (ref "K72") (pin "4") (pinfunction "4_4") (pintype "passive"))
      (node (ref "R45") (pin "2") (pinfunction "2_2") (pintype "passive"))
    )
    (net (code "59") (name "Net-(C38-Pad2)") (class "Default")
      (node (ref "C38") (pin "2") (pinfunction "2_2") (pintype "passive"))
      (node (ref "K73") (pin "4") (pinfunction "4_4") (pintype "passive"))
      (node (ref "K74") (pin "4") (pinfunction "4_4") (pintype "passive"))
      (node (ref "K75") (pin "4") (pinfunction "4_4") (pintype "passive"))
      (node (ref "K76") (pin "4") (pinfunction "4_4") (pintype "passive"))
      (node (ref "K77") (pin "4") (pinfunction "4_4") (pintype "passive"))
      (node (ref "K78") (pin "4") (pinfunction "4_4") (pintype "passive"))
      (node (ref "K79") (pin "4") (pinfunction "4_4") (pintype "passive"))
      (node (ref "K80") (pin "4") (pinfunction "4_4") (pintype "passive"))
      (node (ref "K81") (pin "4") (pinfunction "4_4") (pintype "passive"))
      (node (ref "K82") (pin "4") (pinfunction "4_4") (pintype "passive"))
      (node (ref "K83") (pin "4") (pinfunction "4_4") (pintype "passive"))
      (node (ref "K84") (pin "4") (pinfunction "4_4") (pintype "passive"))
      (node (ref "R47") (pin "2") (pinfunction "2_2") (pintype "passive"))
    )
    (net (code "60") (name "Net-(C39-Pad2)") (class "Default")
      (node (ref "C39") (pin "2") (pinfunction "2_2") (pintype "passive"))
      (node (ref "K85") (pin "4") (pinfunction "4_4") (pintype "passive"))
      (node (ref "K86") (pin "4") (pinfunction "4_4") (pintype "passive"))
      (node (ref "K87") (pin "4") (pinfunction "4_4") (pintype "passive"))
      (node (ref "K88") (pin "4") (pinfunction "4_4") (pintype "passive"))
      (node (ref "K89") (pin "4") (pinfunction "4_4") (pintype "passive"))
      (node (ref "K90") (pin "4") (pinfunction "4_4") (pintype "passive"))
      (node (ref "K91") (pin "4") (pinfunction "4_4") (pintype "passive"))
      (node (ref "K92") (pin "4") (pinfunction "4_4") (pintype "passive"))
      (node (ref "K93") (pin "4") (pinfunction "4_4") (pintype "passive"))
      (node (ref "K94") (pin "4") (pinfunction "4_4") (pintype "passive"))
      (node (ref "K95") (pin "4") (pinfunction "4_4") (pintype "passive"))
      (node (ref "K96") (pin "4") (pinfunction "4_4") (pintype "passive"))
      (node (ref "R49") (pin "2") (pinfunction "2_2") (pintype "passive"))
    )
    (net (code "61") (name "Net-(C40-Pad2)") (class "Default")
      (node (ref "C40") (pin "2") (pinfunction "2_2") (pintype "passive"))
      (node (ref "K100") (pin "4") (pinfunction "4_4") (pintype "passive"))
      (node (ref "K101") (pin "4") (pinfunction "4_4") (pintype "passive"))
      (node (ref "K102") (pin "4") (pinfunction "4_4") (pintype "passive"))
      (node (ref "K103") (pin "4") (pinfunction "4_4") (pintype "passive"))
      (node (ref "K104") (pin "4") (pinfunction "4_4") (pintype "passive"))
      (node (ref "K105") (pin "4") (pinfunction "4_4") (pintype "passive"))
      (node (ref "K106") (pin "4") (pinfunction "4_4") (pintype "passive"))
      (node (ref "K107") (pin "4") (pinfunction "4_4") (pintype "passive"))
      (node (ref "K108") (pin "4") (pinfunction "4_4") (pintype "passive"))
      (node (ref "K97") (pin "4") (pinfunction "4_4") (pintype "passive"))
      (node (ref "K98") (pin "4") (pinfunction "4_4") (pintype "passive"))
      (node (ref "K99") (pin "4") (pinfunction "4_4") (pintype "passive"))
      (node (ref "R50") (pin "2") (pinfunction "2_2") (pintype "passive"))
    )
    (net (code "62") (name "Net-(C41-Pad2)") (class "Default")
      (node (ref "C41") (pin "2") (pinfunction "2_2") (pintype "passive"))
      (node (ref "K109") (pin "4") (pinfunction "4_4") (pintype "passive"))
      (node (ref "K110") (pin "4") (pinfunction "4_4") (pintype "passive"))
      (node (ref "K111") (pin "4") (pinfunction "4_4") (pintype "passive"))
      (node (ref "K112") (pin "4") (pinfunction "4_4") (pintype "passive"))
      (node (ref "K113") (pin "4") (pinfunction "4_4") (pintype "passive"))
      (node (ref "K114") (pin "4") (pinfunction "4_4") (pintype "passive"))
      (node (ref "K115") (pin "4") (pinfunction "4_4") (pintype "passive"))
      (node (ref "K116") (pin "4") (pinfunction "4_4") (pintype "passive"))
      (node (ref "K117") (pin "4") (pinfunction "4_4") (pintype "passive"))
      (node (ref "K118") (pin "4") (pinfunction "4_4") (pintype "passive"))
      (node (ref "K119") (pin "4") (pinfunction "4_4") (pintype "passive"))
      (node (ref "K120") (pin "4") (pinfunction "4_4") (pintype "passive"))
      (node (ref "R51") (pin "2") (pinfunction "2_2") (pintype "passive"))
    )
    (net (code "63") (name "Net-(C42-Pad2)") (class "Default")
      (node (ref "C42") (pin "2") (pinfunction "2_2") (pintype "passive"))
      (node (ref "K121") (pin "4") (pinfunction "4_4") (pintype "passive"))
      (node (ref "K122") (pin "4") (pinfunction "4_4") (pintype "passive"))
      (node (ref "K123") (pin "4") (pinfunction "4_4") (pintype "passive"))
      (node (ref "K124") (pin "4") (pinfunction "4_4") (pintype "passive"))
      (node (ref "K125") (pin "4") (pinfunction "4_4") (pintype "passive"))
      (node (ref "K126") (pin "4") (pinfunction "4_4") (pintype "passive"))
      (node (ref "K127") (pin "4") (pinfunction "4_4") (pintype "passive"))
      (node (ref "K128") (pin "4") (pinfunction "4_4") (pintype "passive"))
      (node (ref "K129") (pin "4") (pinfunction "4_4") (pintype "passive"))
      (node (ref "K130") (pin "4") (pinfunction "4_4") (pintype "passive"))
      (node (ref "K131") (pin "4") (pinfunction "4_4") (pintype "passive"))
      (node (ref "K132") (pin "4") (pinfunction "4_4") (pintype "passive"))
      (node (ref "R52") (pin "2") (pinfunction "2_2") (pintype "passive"))
    )
    (net (code "64") (name "Net-(C43-Pad2)") (class "Default")
      (node (ref "C43") (pin "2") (pinfunction "2_2") (pintype "passive"))
      (node (ref "K133") (pin "4") (pinfunction "4_4") (pintype "passive"))
      (node (ref "K134") (pin "4") (pinfunction "4_4") (pintype "passive"))
      (node (ref "K135") (pin "4") (pinfunction "4_4") (pintype "passive"))
      (node (ref "K136") (pin "4") (pinfunction "4_4") (pintype "passive"))
      (node (ref "K137") (pin "4") (pinfunction "4_4") (pintype "passive"))
      (node (ref "K138") (pin "4") (pinfunction "4_4") (pintype "passive"))
      (node (ref "K139") (pin "4") (pinfunction "4_4") (pintype "passive"))
      (node (ref "K140") (pin "4") (pinfunction "4_4") (pintype "passive"))
      (node (ref "K141") (pin "4") (pinfunction "4_4") (pintype "passive"))
      (node (ref "K142") (pin "4") (pinfunction "4_4") (pintype "passive"))
      (node (ref "K143") (pin "4") (pinfunction "4_4") (pintype "passive"))
      (node (ref "K144") (pin "4") (pinfunction "4_4") (pintype "passive"))
      (node (ref "R53") (pin "2") (pinfunction "2_2") (pintype "passive"))
    )
    (net (code "65") (name "Net-(K1-Pad1)") (class "Default")
      (node (ref "K1") (pin "1") (pinfunction "1_1") (pintype "passive"))
      (node (ref "K10") (pin "1") (pinfunction "1_1") (pintype "passive"))
      (node (ref "K11") (pin "1") (pinfunction "1_1") (pintype "passive"))
      (node (ref "K12") (pin "1") (pinfunction "1_1") (pintype "passive"))
      (node (ref "K2") (pin "1") (pinfunction "1_1") (pintype "passive"))
      (node (ref "K3") (pin "1") (pinfunction "1_1") (pintype "passive"))
      (node (ref "K4") (pin "1") (pinfunction "1_1") (pintype "passive"))
      (node (ref "K5") (pin "1") (pinfunction "1_1") (pintype "passive"))
      (node (ref "K6") (pin "1") (pinfunction "1_1") (pintype "passive"))
      (node (ref "K7") (pin "1") (pinfunction "1_1") (pintype "passive"))
      (node (ref "K8") (pin "1") (pinfunction "1_1") (pintype "passive"))
      (node (ref "K9") (pin "1") (pinfunction "1_1") (pintype "passive"))
      (node (ref "R34") (pin "2") (pinfunction "2_2") (pintype "passive"))
    )
    (net (code "66") (name "Net-(K13-Pad1)") (class "Default")
      (node (ref "K13") (pin "1") (pinfunction "1_1") (pintype "passive"))
      (node (ref "K14") (pin "1") (pinfunction "1_1") (pintype "passive"))
      (node (ref "K15") (pin "1") (pinfunction "1_1") (pintype "passive"))
      (node (ref "K16") (pin "1") (pinfunction "1_1") (pintype "passive"))
      (node (ref "K17") (pin "1") (pinfunction "1_1") (pintype "passive"))
      (node (ref "K18") (pin "1") (pinfunction "1_1") (pintype "passive"))
      (node (ref "K19") (pin "1") (pinfunction "1_1") (pintype "passive"))
      (node (ref "K20") (pin "1") (pinfunction "1_1") (pintype "passive"))
      (node (ref "K21") (pin "1") (pinfunction "1_1") (pintype "passive"))
      (node (ref "K22") (pin "1") (pinfunction "1_1") (pintype "passive"))
      (node (ref "K23") (pin "1") (pinfunction "1_1") (pintype "passive"))
      (node (ref "K24") (pin "1") (pinfunction "1_1") (pintype "passive"))
      (node (ref "R36") (pin "2") (pinfunction "2_2") (pintype "passive"))
    )
    (net (code "67") (name "Net-(K25-Pad1)") (class "Default")
      (node (ref "K25") (pin "1") (pinfunction "1_1") (pintype "passive"))
      (node (ref "K26") (pin "1") (pinfunction "1_1") (pintype "passive"))
      (node (ref "K27") (pin "1") (pinfunction "1_1") (pintype "passive"))
      (node (ref "K28") (pin "1") (pinfunction "1_1") (pintype "passive"))
      (node (ref "K29") (pin "1") (pinfunction "1_1") (pintype "passive"))
      (node (ref "K30") (pin "1") (pinfunction "1_1") (pintype "passive"))
      (node (ref "K31") (pin "1") (pinfunction "1_1") (pintype "passive"))
      (node (ref "K32") (pin "1") (pinfunction "1_1") (pintype "passive"))
      (node (ref "K33") (pin "1") (pinfunction "1_1") (pintype "passive"))
      (node (ref "K34") (pin "1") (pinfunction "1_1") (pintype "passive"))
      (node (ref "K35") (pin "1") (pinfunction "1_1") (pintype "passive"))
      (node (ref "K36") (pin "1") (pinfunction "1_1") (pintype "passive"))
      (node (ref "R38") (pin "2") (pinfunction "2_2") (pintype "passive"))
    )
    (net (code "68") (name "Net-(K37-Pad1)") (class "Default")
      (node (ref "K37") (pin "1") (pinfunction "1_1") (pintype "passive"))
      (node (ref "K38") (pin "1") (pinfunction "1_1") (pintype "passive"))
      (node (ref "K39") (pin "1") (pinfunction "1_1") (pintype "passive"))
      (node (ref "K40") (pin "1") (pinfunction "1_1") (pintype "passive"))
      (node (ref "K41") (pin "1") (pinfunction "1_1") (pintype "passive"))
      (node (ref "K42") (pin "1") (pinfunction "1_1") (pintype "passive"))
      (node (ref "K43") (pin "1") (pinfunction "1_1") (pintype "passive"))
      (node (ref "K44") (pin "1") (pinfunction "1_1") (pintype "passive"))
      (node (ref "K45") (pin "1") (pinfunction "1_1") (pintype "passive"))
      (node (ref "K46") (pin "1") (pinfunction "1_1") (pintype "passive"))
      (node (ref "K47") (pin "1") (pinfunction "1_1") (pintype "passive"))
      (node (ref "K48") (pin "1") (pinfunction "1_1") (pintype "passive"))
      (node (ref "R40") (pin "2") (pinfunction "2_2") (pintype "passive"))
    )
    (net (code "69") (name "Net-(K49-Pad1)") (class "Default")
      (node (ref "K49") (pin "1") (pinfunction "1_1") (pintype "passive"))
      (node (ref "K50") (pin "1") (pinfunction "1_1") (pintype "passive"))
      (node (ref "K51") (pin "1") (pinfunction "1_1") (pintype "passive"))
      (node (ref "K52") (pin "1") (pinfunction "1_1") (pintype "passive"))
      (node (ref "K53") (pin "1") (pinfunction "1_1") (pintype "passive"))
      (node (ref "K54") (pin "1") (pinfunction "1_1") (pintype "passive"))
      (node (ref "K55") (pin "1") (pinfunction "1_1") (pintype "passive"))
      (node (ref "K56") (pin "1") (pinfunction "1_1") (pintype "passive"))
      (node (ref "K57") (pin "1") (pinfunction "1_1") (pintype "passive"))
      (node (ref "K58") (pin "1") (pinfunction "1_1") (pintype "passive"))
      (node (ref "K59") (pin "1") (pinfunction "1_1") (pintype "passive"))
      (node (ref "K60") (pin "1") (pinfunction "1_1") (pintype "passive"))
      (node (ref "R42") (pin "2") (pinfunction "2_2") (pintype "passive"))
    )
    (net (code "70") (name "Net-(K61-Pad1)") (class "Default")
      (node (ref "K61") (pin "1") (pinfunction "1_1") (pintype "passive"))
      (node (ref "K62") (pin "1") (pinfunction "1_1") (pintype "passive"))
      (node (ref "K63") (pin "1") (pinfunction "1_1") (pintype "passive"))
      (node (ref "K64") (pin "1") (pinfunction "1_1") (pintype "passive"))
      (node (ref "K65") (pin "1") (pinfunction "1_1") (pintype "passive"))
      (node (ref "K66") (pin "1") (pinfunction "1_1") (pintype "passive"))
      (node (ref "K67") (pin "1") (pinfunction "1_1") (pintype "passive"))
      (node (ref "K68") (pin "1") (pinfunction "1_1") (pintype "passive"))
      (node (ref "K69") (pin "1") (pinfunction "1_1") (pintype "passive"))
      (node (ref "K70") (pin "1") (pinfunction "1_1") (pintype "passive"))
      (node (ref "K71") (pin "1") (pinfunction "1_1") (pintype "passive"))
      (node (ref "K72") (pin "1") (pinfunction "1_1") (pintype "passive"))
      (node (ref "R44") (pin "2") (pinfunction "2_2") (pintype "passive"))
    )
    (net (code "71") (name "Net-(K73-Pad1)") (class "Default")
      (node (ref "K73") (pin "1") (pinfunction "1_1") (pintype "passive"))
      (node (ref "K74") (pin "1") (pinfunction "1_1") (pintype "passive"))
      (node (ref "K75") (pin "1") (pinfunction "1_1") (pintype "passive"))
      (node (ref "K76") (pin "1") (pinfunction "1_1") (pintype "passive"))
      (node (ref "K77") (pin "1") (pinfunction "1_1") (pintype "passive"))
      (node (ref "K78") (pin "1") (pinfunction "1_1") (pintype "passive"))
      (node (ref "K79") (pin "1") (pinfunction "1_1") (pintype "passive"))
      (node (ref "K80") (pin "1") (pinfunction "1_1") (pintype "passive"))
      (node (ref "K81") (pin "1") (pinfunction "1_1") (pintype "passive"))
      (node (ref "K82") (pin "1") (pinfunction "1_1") (pintype "passive"))
      (node (ref "K83") (pin "1") (pinfunction "1_1") (pintype "passive"))
      (node (ref "K84") (pin "1") (pinfunction "1_1") (pintype "passive"))
      (node (ref "R46") (pin "2") (pinfunction "2_2") (pintype "passive"))
    )
    (net (code "72") (name "Net-(K85-Pad1)") (class "Default")
      (node (ref "K85") (pin "1") (pinfunction "1_1") (pintype "passive"))
      (node (ref "K86") (pin "1") (pinfunction "1_1") (pintype "passive"))
      (node (ref "K87") (pin "1") (pinfunction "1_1") (pintype "passive"))
      (node (ref "K88") (pin "1") (pinfunction "1_1") (pintype "passive"))
      (node (ref "K89") (pin "1") (pinfunction "1_1") (pintype "passive"))
      (node (ref "K90") (pin "1") (pinfunction "1_1") (pintype "passive"))
      (node (ref "K91") (pin "1") (pinfunction "1_1") (pintype "passive"))
      (node (ref "K92") (pin "1") (pinfunction "1_1") (pintype "passive"))
      (node (ref "K93") (pin "1") (pinfunction "1_1") (pintype "passive"))
      (node (ref "K94") (pin "1") (pinfunction "1_1") (pintype "passive"))
      (node (ref "K95") (pin "1") (pinfunction "1_1") (pintype "passive"))
      (node (ref "K96") (pin "1") (pinfunction "1_1") (pintype "passive"))
      (node (ref "R48") (pin "2") (pinfunction "2_2") (pintype "passive"))
    )
    (net (code "73") (name "unconnected-(K9-Pad2)") (class "Default")
      (node (ref "K9") (pin "2") (pinfunction "2_2") (pintype "passive"))
    )
    (net (code "74") (name "unconnected-(K10-Pad2)") (class "Default")
      (node (ref "K10") (pin "2") (pinfunction "2_2") (pintype "passive"))
    )
    (net (code "75") (name "unconnected-(K11-Pad2)") (class "Default")
      (node (ref "K11") (pin "2") (pinfunction "2_2") (pintype "passive"))
    )
    (net (code "76") (name "unconnected-(K12-Pad2)") (class "Default")
      (node (ref "K12") (pin "2") (pinfunction "2_2") (pintype "passive"))
    )
    (net (code "77") (name "unconnected-(K21-Pad2)") (class "Default")
      (node (ref "K21") (pin "2") (pinfunction "2_2") (pintype "passive"))
    )
    (net (code "78") (name "unconnected-(K22-Pad2)") (class "Default")
      (node (ref "K22") (pin "2") (pinfunction "2_2") (pintype "passive"))
    )
    (net (code "79") (name "unconnected-(K23-Pad2)") (class "Default")
      (node (ref "K23") (pin "2") (pinfunction "2_2") (pintype "passive"))
    )
    (net (code "80") (name "unconnected-(K24-Pad2)") (class "Default")
      (node (ref "K24") (pin "2") (pinfunction "2_2") (pintype "passive"))
    )
    (net (code "81") (name "unconnected-(K33-Pad2)") (class "Default")
      (node (ref "K33") (pin "2") (pinfunction "2_2") (pintype "passive"))
    )
    (net (code "82") (name "unconnected-(K34-Pad2)") (class "Default")
      (node (ref "K34") (pin "2") (pinfunction "2_2") (pintype "passive"))
    )
    (net (code "83") (name "unconnected-(K35-Pad2)") (class "Default")
      (node (ref "K35") (pin "2") (pinfunction "2_2") (pintype "passive"))
    )
    (net (code "84") (name "unconnected-(K36-Pad2)") (class "Default")
      (node (ref "K36") (pin "2") (pinfunction "2_2") (pintype "passive"))
    )
    (net (code "85") (name "unconnected-(K45-Pad2)") (class "Default")
      (node (ref "K45") (pin "2") (pinfunction "2_2") (pintype "passive"))
    )
    (net (code "86") (name "unconnected-(K46-Pad2)") (class "Default")
      (node (ref "K46") (pin "2") (pinfunction "2_2") (pintype "passive"))
    )
    (net (code "87") (name "unconnected-(K47-Pad2)") (class "Default")
      (node (ref "K47") (pin "2") (pinfunction "2_2") (pintype "passive"))
    )
    (net (code "88") (name "unconnected-(K48-Pad2)") (class "Default")
      (node (ref "K48") (pin "2") (pinfunction "2_2") (pintype "passive"))
    )
    (net (code "89") (name "unconnected-(K57-Pad2)") (class "Default")
      (node (ref "K57") (pin "2") (pinfunction "2_2") (pintype "passive"))
    )
    (net (code "90") (name "unconnected-(K58-Pad2)") (class "Default")
      (node (ref "K58") (pin "2") (pinfunction "2_2") (pintype "passive"))
    )
    (net (code "91") (name "unconnected-(K59-Pad2)") (class "Default")
      (node (ref "K59") (pin "2") (pinfunction "2_2") (pintype "passive"))
    )
    (net (code "92") (name "unconnected-(K60-Pad2)") (class "Default")
      (node (ref "K60") (pin "2") (pinfunction "2_2") (pintype "passive"))
    )
    (net (code "93") (name "unconnected-(K69-Pad2)") (class "Default")
      (node (ref "K69") (pin "2") (pinfunction "2_2") (pintype "passive"))
    )
    (net (code "94") (name "unconnected-(K70-Pad2)") (class "Default")
      (node (ref "K70") (pin "2") (pinfunction "2_2") (pintype "passive"))
    )
    (net (code "95") (name "unconnected-(K71-Pad2)") (class "Default")
      (node (ref "K71") (pin "2") (pinfunction "2_2") (pintype "passive"))
    )
    (net (code "96") (name "unconnected-(K72-Pad2)") (class "Default")
      (node (ref "K72") (pin "2") (pinfunction "2_2") (pintype "passive"))
    )
    (net (code "97") (name "unconnected-(K81-Pad2)") (class "Default")
      (node (ref "K81") (pin "2") (pinfunction "2_2") (pintype "passive"))
    )
    (net (code "98") (name "unconnected-(K82-Pad2)") (class "Default")
      (node (ref "K82") (pin "2") (pinfunction "2_2") (pintype "passive"))
    )
    (net (code "99") (name "unconnected-(K83-Pad2)") (class "Default")
      (node (ref "K83") (pin "2") (pinfunction "2_2") (pintype "passive"))
    )
    (net (code "100") (name "unconnected-(K84-Pad2)") (class "Default")
      (node (ref "K84") (pin "2") (pinfunction "2_2") (pintype "passive"))
    )
    (net (code "101") (name "unconnected-(K93-Pad2)") (class "Default")
      (node (ref "K93") (pin "2") (pinfunction "2_2") (pintype "passive"))
    )
    (net (code "102") (name "unconnected-(K94-Pad2)") (class "Default")
      (node (ref "K94") (pin "2") (pinfunction "2_2") (pintype "passive"))
    )
    (net (code "103") (name "unconnected-(K95-Pad2)") (class "Default")
      (node (ref "K95") (pin "2") (pinfunction "2_2") (pintype "passive"))
    )
    (net (code "104") (name "unconnected-(K96-Pad2)") (class "Default")
      (node (ref "K96") (pin "2") (pinfunction "2_2") (pintype "passive"))
    )
    (net (code "105") (name "unconnected-(K97-Pad1)") (class "Default")
      (node (ref "K97") (pin "1") (pinfunction "1_1") (pintype "passive"))
    )
    (net (code "106") (name "unconnected-(K98-Pad1)") (class "Default")
      (node (ref "K98") (pin "1") (pinfunction "1_1") (pintype "passive"))
    )
    (net (code "107") (name "unconnected-(K99-Pad1)") (class "Default")
      (node (ref "K99") (pin "1") (pinfunction "1_1") (pintype "passive"))
    )
    (net (code "108") (name "unconnected-(K100-Pad1)") (class "Default")
      (node (ref "K100") (pin "1") (pinfunction "1_1") (pintype "passive"))
    )
    (net (code "109") (name "unconnected-(K101-Pad1)") (class "Default")
      (node (ref "K101") (pin "1") (pinfunction "1_1") (pintype "passive"))
    )
    (net (code "110") (name "unconnected-(K102-Pad1)") (class "Default")
      (node (ref "K102") (pin "1") (pinfunction "1_1") (pintype "passive"))
    )
    (net (code "111") (name "unconnected-(K103-Pad1)") (class "Default")
      (node (ref "K103") (pin "1") (pinfunction "1_1") (pintype "passive"))
    )
    (net (code "112") (name "unconnected-(K104-Pad1)") (class "Default")
      (node (ref "K104") (pin "1") (pinfunction "1_1") (pintype "passive"))
    )
    (net (code "113") (name "unconnected-(K105-Pad1)") (class "Default")
      (node (ref "K105") (pin "1") (pinfunction "1_1") (pintype "passive"))
    )
    (net (code "114") (name "unconnected-(K105-Pad2)") (class "Default")
      (node (ref "K105") (pin "2") (pinfunction "2_2") (pintype "passive"))
    )
    (net (code "115") (name "unconnected-(K106-Pad1)") (class "Default")
      (node (ref "K106") (pin "1") (pinfunction "1_1") (pintype "passive"))
    )
    (net (code "116") (name "unconnected-(K106-Pad2)") (class "Default")
      (node (ref "K106") (pin "2") (pinfunction "2_2") (pintype "passive"))
    )
    (net (code "117") (name "unconnected-(K107-Pad1)") (class "Default")
      (node (ref "K107") (pin "1") (pinfunction "1_1") (pintype "passive"))
    )
    (net (code "118") (name "unconnected-(K107-Pad2)") (class "Default")
      (node (ref "K107") (pin "2") (pinfunction "2_2") (pintype "passive"))
    )
    (net (code "119") (name "unconnected-(K108-Pad1)") (class "Default")
      (node (ref "K108") (pin "1") (pinfunction "1_1") (pintype "passive"))
    )
    (net (code "120") (name "unconnected-(K108-Pad2)") (class "Default")
      (node (ref "K108") (pin "2") (pinfunction "2_2") (pintype "passive"))
    )
    (net (code "121") (name "unconnected-(K109-Pad1)") (class "Default")
      (node (ref "K109") (pin "1") (pinfunction "1_1") (pintype "passive"))
    )
    (net (code "122") (name "unconnected-(K110-Pad1)") (class "Default")
      (node (ref "K110") (pin "1") (pinfunction "1_1") (pintype "passive"))
    )
    (net (code "123") (name "unconnected-(K111-Pad1)") (class "Default")
      (node (ref "K111") (pin "1") (pinfunction "1_1") (pintype "passive"))
    )
    (net (code "124") (name "unconnected-(K112-Pad1)") (class "Default")
      (node (ref "K112") (pin "1") (pinfunction "1_1") (pintype "passive"))
    )
    (net (code "125") (name "unconnected-(K113-Pad1)") (class "Default")
      (node (ref "K113") (pin "1") (pinfunction "1_1") (pintype "passive"))
    )
    (net (code "126") (name "unconnected-(K114-Pad1)") (class "Default")
      (node (ref "K114") (pin "1") (pinfunction "1_1") (pintype "passive"))
    )
    (net (code "127") (name "unconnected-(K115-Pad1)") (class "Default")
      (node (ref "K115") (pin "1") (pinfunction "1_1") (pintype "passive"))
    )
    (net (code "128") (name "unconnected-(K116-Pad1)") (class "Default")
      (node (ref "K116") (pin "1") (pinfunction "1_1") (pintype "passive"))
    )
    (net (code "129") (name "unconnected-(K117-Pad1)") (class "Default")
      (node (ref "K117") (pin "1") (pinfunction "1_1") (pintype "passive"))
    )
    (net (code "130") (name "unconnected-(K117-Pad2)") (class "Default")
      (node (ref "K117") (pin "2") (pinfunction "2_2") (pintype "passive"))
    )
    (net (code "131") (name "unconnected-(K118-Pad1)") (class "Default")
      (node (ref "K118") (pin "1") (pinfunction "1_1") (pintype "passive"))
    )
    (net (code "132") (name "unconnected-(K118-Pad2)") (class "Default")
      (node (ref "K118") (pin "2") (pinfunction "2_2") (pintype "passive"))
    )
    (net (code "133") (name "unconnected-(K119-Pad1)") (class "Default")
      (node (ref "K119") (pin "1") (pinfunction "1_1") (pintype "passive"))
    )
    (net (code "134") (name "unconnected-(K119-Pad2)") (class "Default")
      (node (ref "K119") (pin "2") (pinfunction "2_2") (pintype "passive"))
    )
    (net (code "135") (name "unconnected-(K120-Pad1)") (class "Default")
      (node (ref "K120") (pin "1") (pinfunction "1_1") (pintype "passive"))
    )
    (net (code "136") (name "unconnected-(K120-Pad2)") (class "Default")
      (node (ref "K120") (pin "2") (pinfunction "2_2") (pintype "passive"))
    )
    (net (code "137") (name "unconnected-(K121-Pad1)") (class "Default")
      (node (ref "K121") (pin "1") (pinfunction "1_1") (pintype "passive"))
    )
    (net (code "138") (name "unconnected-(K122-Pad1)") (class "Default")
      (node (ref "K122") (pin "1") (pinfunction "1_1") (pintype "passive"))
    )
    (net (code "139") (name "unconnected-(K123-Pad1)") (class "Default")
      (node (ref "K123") (pin "1") (pinfunction "1_1") (pintype "passive"))
    )
    (net (code "140") (name "unconnected-(K124-Pad1)") (class "Default")
      (node (ref "K124") (pin "1") (pinfunction "1_1") (pintype "passive"))
    )
    (net (code "141") (name "unconnected-(K125-Pad1)") (class "Default")
      (node (ref "K125") (pin "1") (pinfunction "1_1") (pintype "passive"))
    )
    (net (code "142") (name "unconnected-(K126-Pad1)") (class "Default")
      (node (ref "K126") (pin "1") (pinfunction "1_1") (pintype "passive"))
    )
    (net (code "143") (name "unconnected-(K127-Pad1)") (class "Default")
      (node (ref "K127") (pin "1") (pinfunction "1_1") (pintype "passive"))
    )
    (net (code "144") (name "unconnected-(K128-Pad1)") (class "Default")
      (node (ref "K128") (pin "1") (pinfunction "1_1") (pintype "passive"))
    )
    (net (code "145") (name "unconnected-(K129-Pad1)") (class "Default")
      (node (ref "K129") (pin "1") (pinfunction "1_1") (pintype "passive"))
    )
    (net (code "146") (name "unconnected-(K129-Pad2)") (class "Default")
      (node (ref "K129") (pin "2") (pinfunction "2_2") (pintype "passive"))
    )
    (net (code "147") (name "unconnected-(K130-Pad1)") (class "Default")
      (node (ref "K130") (pin "1") (pinfunction "1_1") (pintype "passive"))
    )
    (net (code "148") (name "unconnected-(K130-Pad2)") (class "Default")
      (node (ref "K130") (pin "2") (pinfunction "2_2") (pintype "passive"))
    )
    (net (code "149") (name "unconnected-(K131-Pad1)") (class "Default")
      (node (ref "K131") (pin "1") (pinfunction "1_1") (pintype "passive"))
    )
    (net (code "150") (name "unconnected-(K131-Pad2)") (class "Default")
      (node (ref "K131") (pin "2") (pinfunction "2_2") (pintype "passive"))
    )
    (net (code "151") (name "unconnected-(K132-Pad1)") (class "Default")
      (node (ref "K132") (pin "1") (pinfunction "1_1") (pintype "passive"))
    )
    (net (code "152") (name "unconnected-(K132-Pad2)") (class "Default")
      (node (ref "K132") (pin "2") (pinfunction "2_2") (pintype "passive"))
    )
    (net (code "153") (name "unconnected-(K133-Pad1)") (class "Default")
      (node (ref "K133") (pin "1") (pinfunction "1_1") (pintype "passive"))
    )
    (net (code "154") (name "unconnected-(K134-Pad1)") (class "Default")
      (node (ref "K134") (pin "1") (pinfunction "1_1") (pintype "passive"))
    )
    (net (code "155") (name "unconnected-(K135-Pad1)") (class "Default")
      (node (ref "K135") (pin "1") (pinfunction "1_1") (pintype "passive"))
    )
    (net (code "156") (name "unconnected-(K136-Pad1)") (class "Default")
      (node (ref "K136") (pin "1") (pinfunction "1_1") (pintype "passive"))
    )
    (net (code "157") (name "unconnected-(K137-Pad1)") (class "Default")
      (node (ref "K137") (pin "1") (pinfunction "1_1") (pintype "passive"))
    )
    (net (code "158") (name "unconnected-(K138-Pad1)") (class "Default")
      (node (ref "K138") (pin "1") (pinfunction "1_1") (pintype "passive"))
    )
    (net (code "159") (name "unconnected-(K139-Pad1)") (class "Default")
      (node (ref "K139") (pin "1") (pinfunction "1_1") (pintype "passive"))
    )
    (net (code "160") (name "unconnected-(K140-Pad1)") (class "Default")
      (node (ref "K140") (pin "1") (pinfunction "1_1") (pintype "passive"))
    )
    (net (code "161") (name "unconnected-(K141-Pad1)") (class "Default")
      (node (ref "K141") (pin "1") (pinfunction "1_1") (pintype "passive"))
    )
    (net (code "162") (name "unconnected-(K141-Pad2)") (class "Default")
      (node (ref "K141") (pin "2") (pinfunction "2_2") (pintype "passive"))
    )
    (net (code "163") (name "unconnected-(K142-Pad1)") (class "Default")
      (node (ref "K142") (pin "1") (pinfunction "1_1") (pintype "passive"))
    )
    (net (code "164") (name "unconnected-(K142-Pad2)") (class "Default")
      (node (ref "K142") (pin "2") (pinfunction "2_2") (pintype "passive"))
    )
    (net (code "165") (name "unconnected-(K143-Pad1)") (class "Default")
      (node (ref "K143") (pin "1") (pinfunction "1_1") (pintype "passive"))
    )
    (net (code "166") (name "unconnected-(K143-Pad2)") (class "Default")
      (node (ref "K143") (pin "2") (pinfunction "2_2") (pintype "passive"))
    )
    (net (code "167") (name "unconnected-(K144-Pad1)") (class "Default")
      (node (ref "K144") (pin "1") (pinfunction "1_1") (pintype "passive"))
    )
    (net (code "168") (name "unconnected-(K144-Pad2)") (class "Default")
      (node (ref "K144") (pin "2") (pinfunction "2_2") (pintype "passive"))
    )
  )
)
